# EEZ_DIB_MCU_r1B1.net
KiCad netlist of a schematic drawn in EAGLE
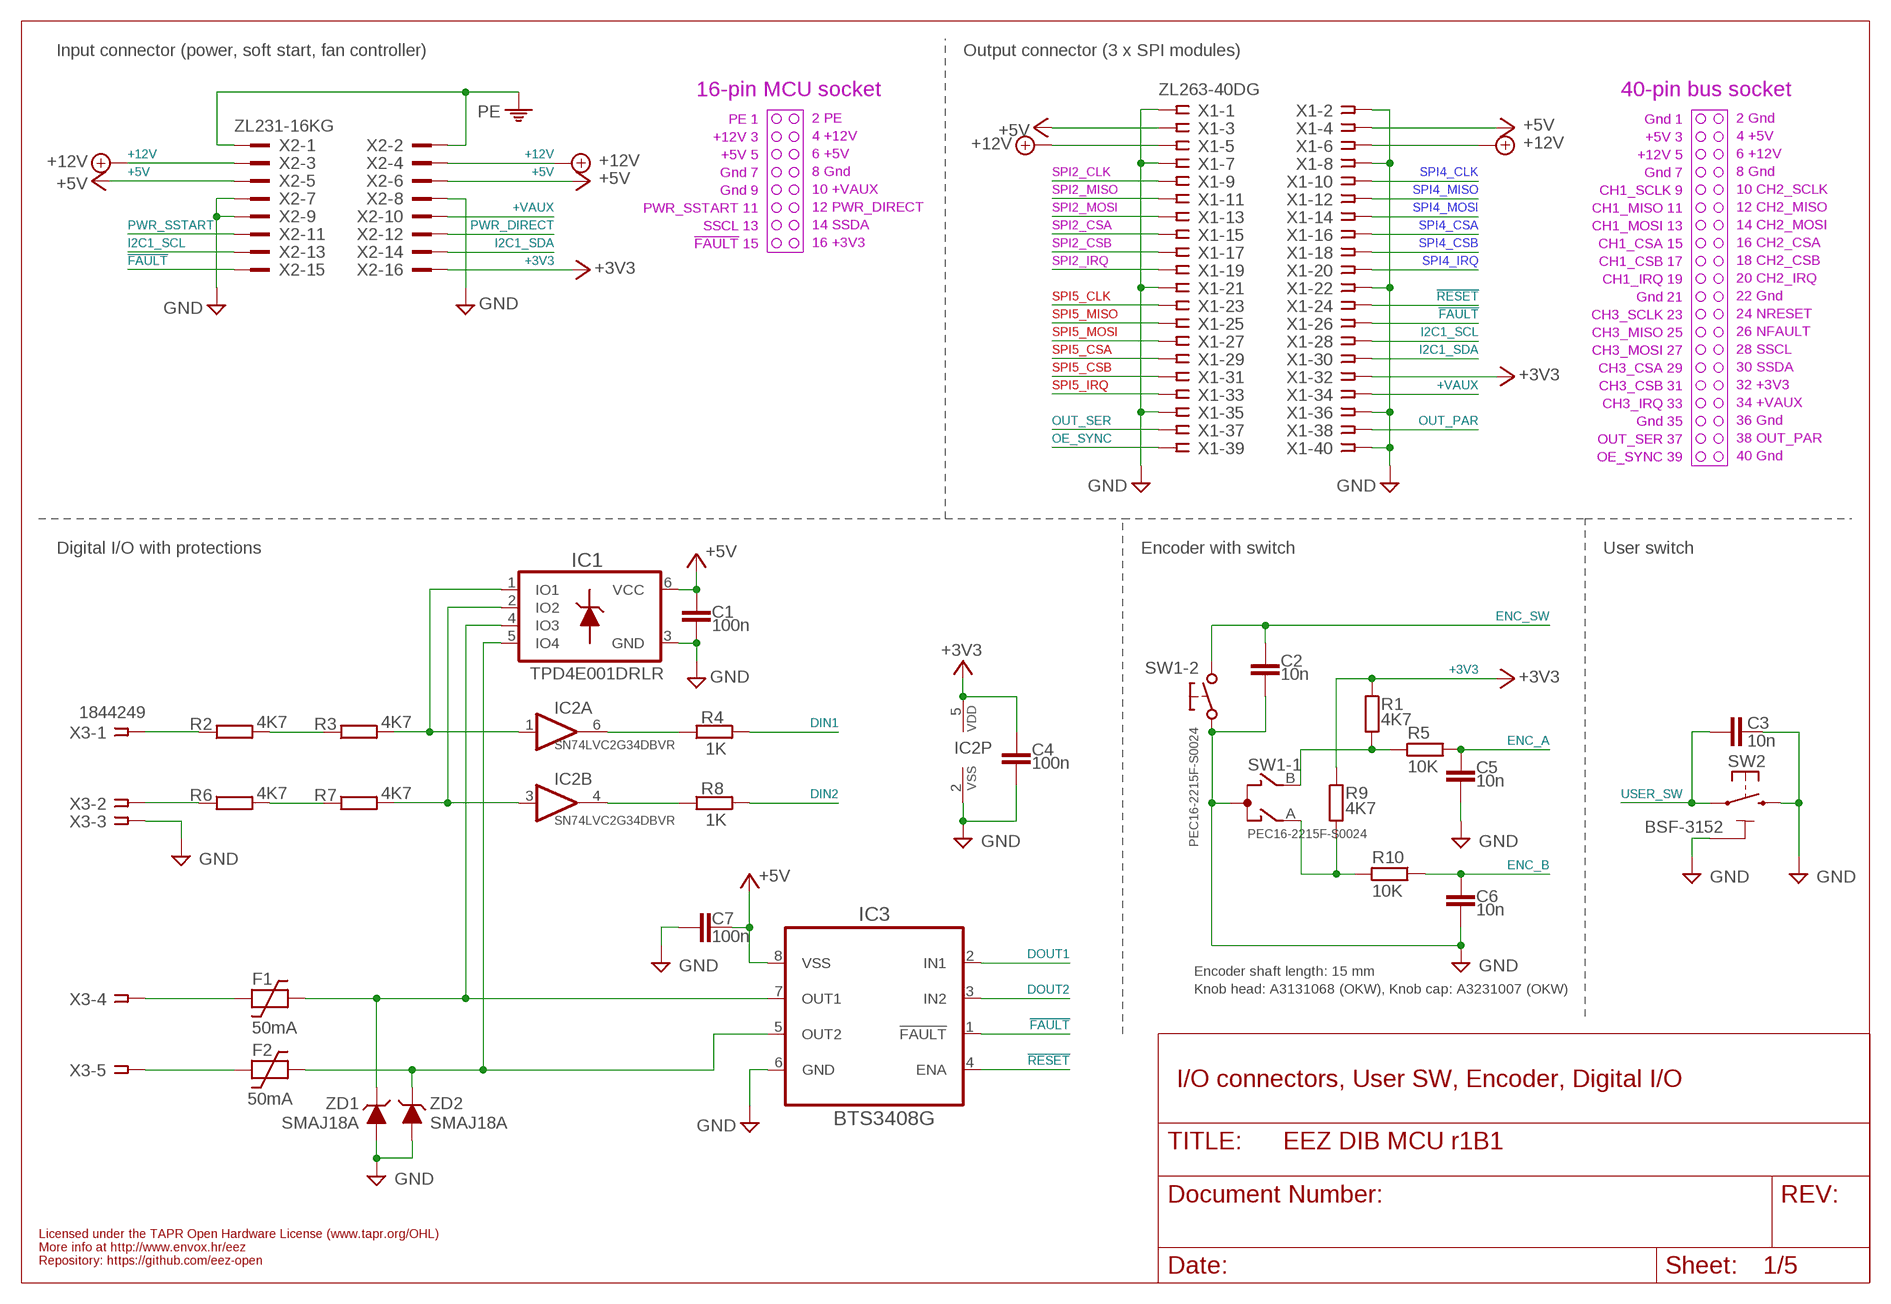
[diagram p0: schematic, sheet 1]
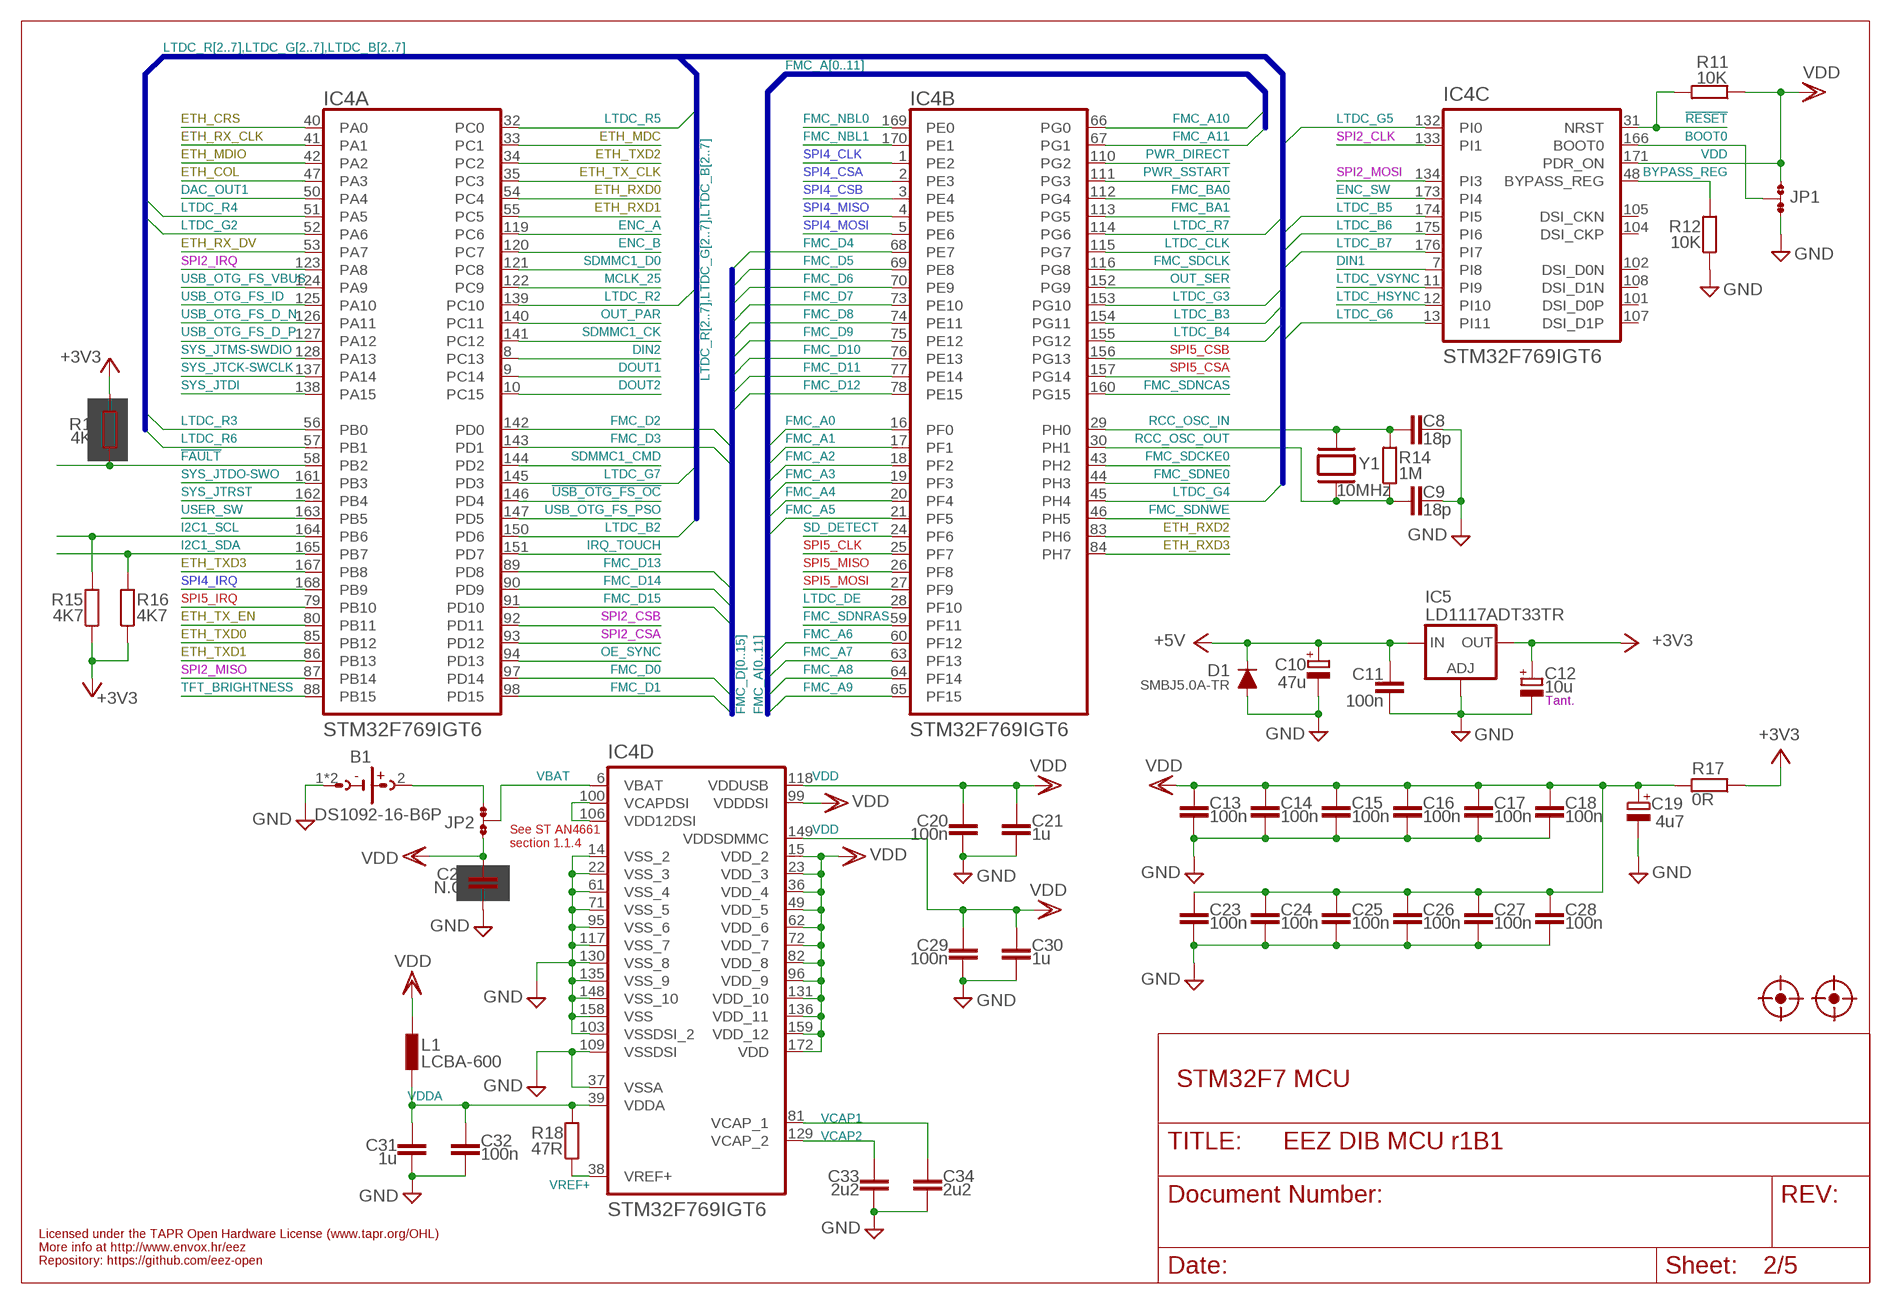
[diagram p1: schematic, sheet 2]
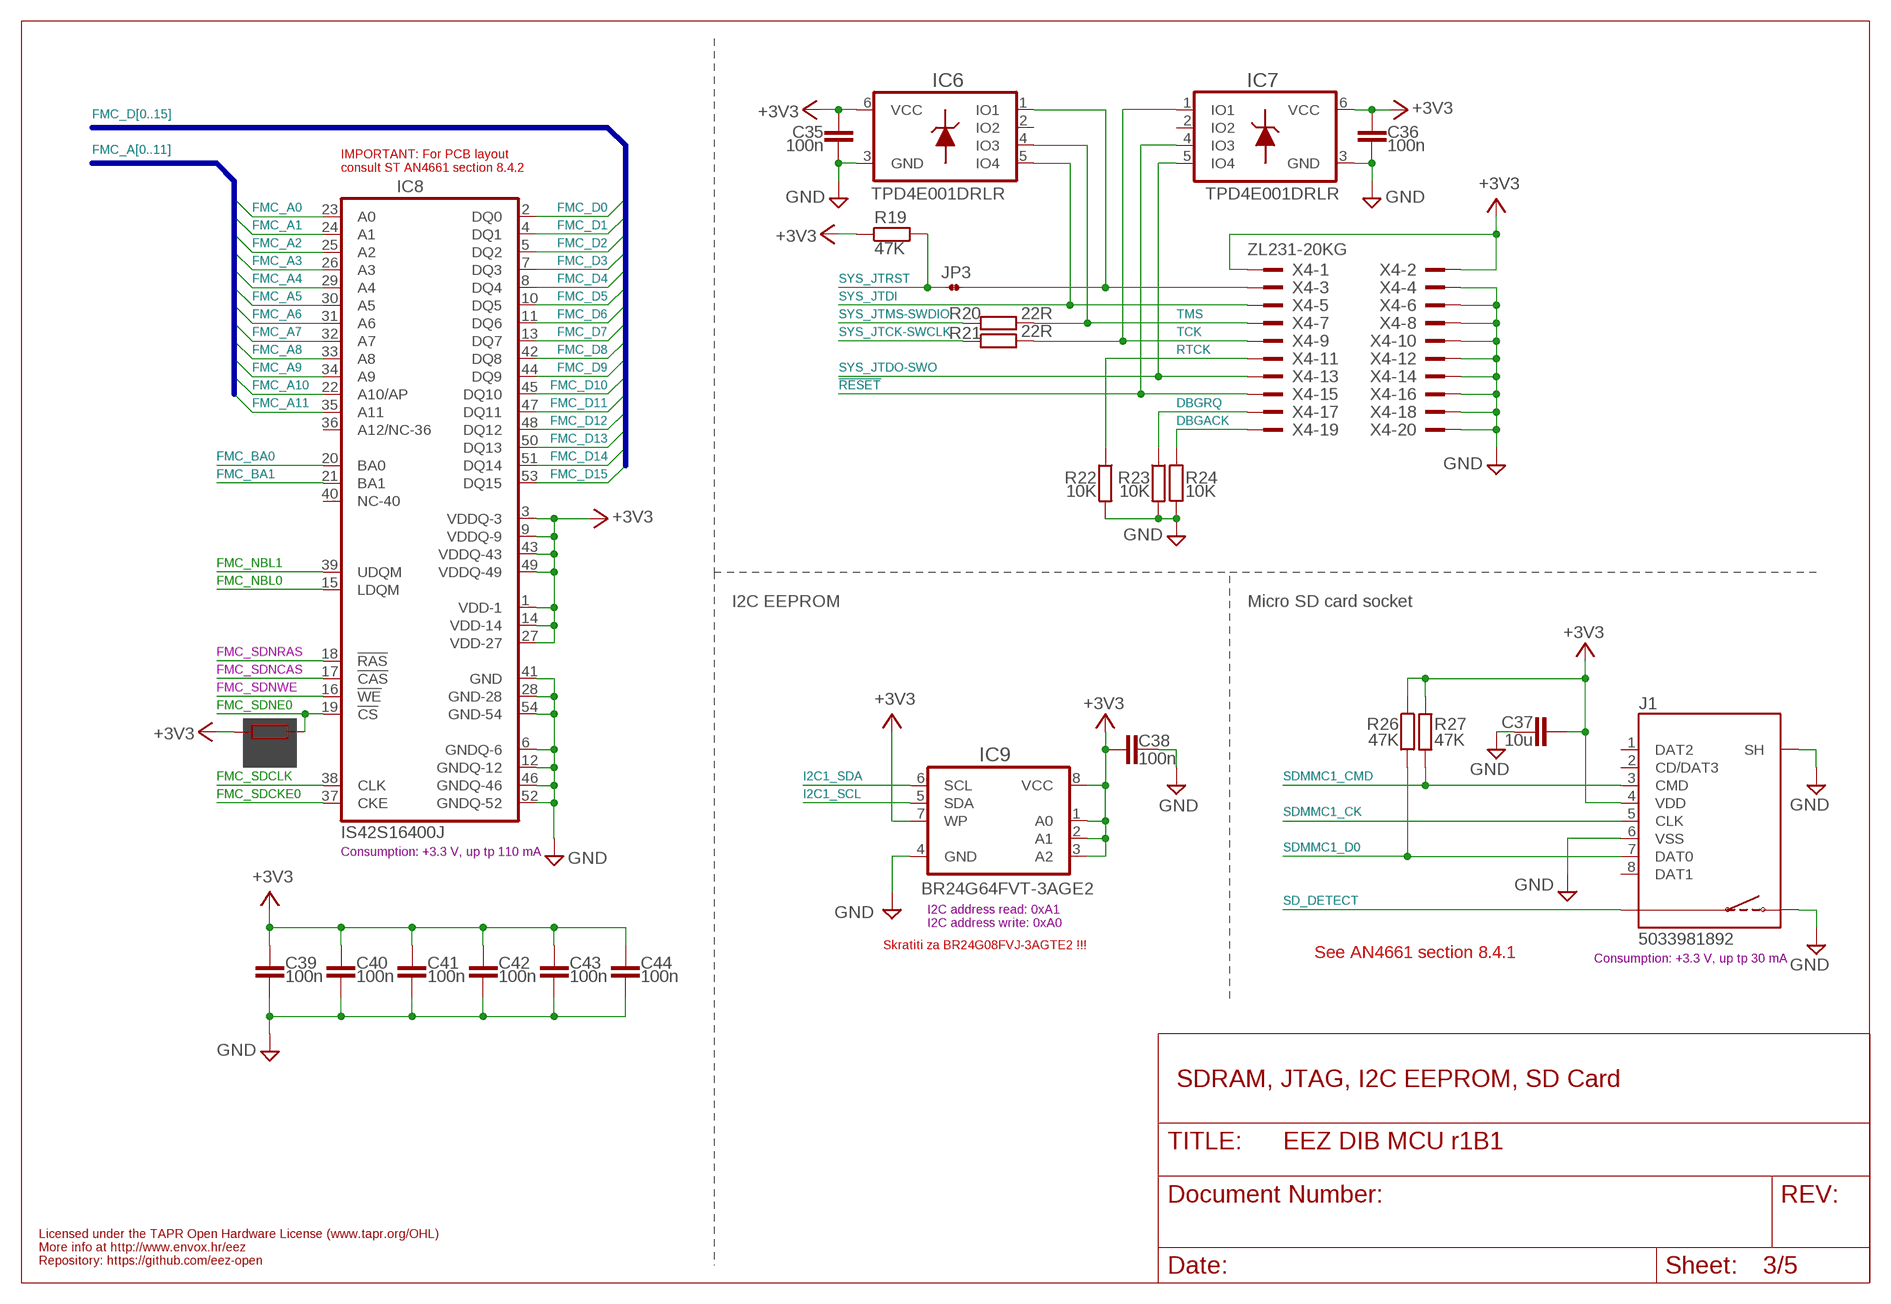
[diagram p2: schematic, sheet 3]
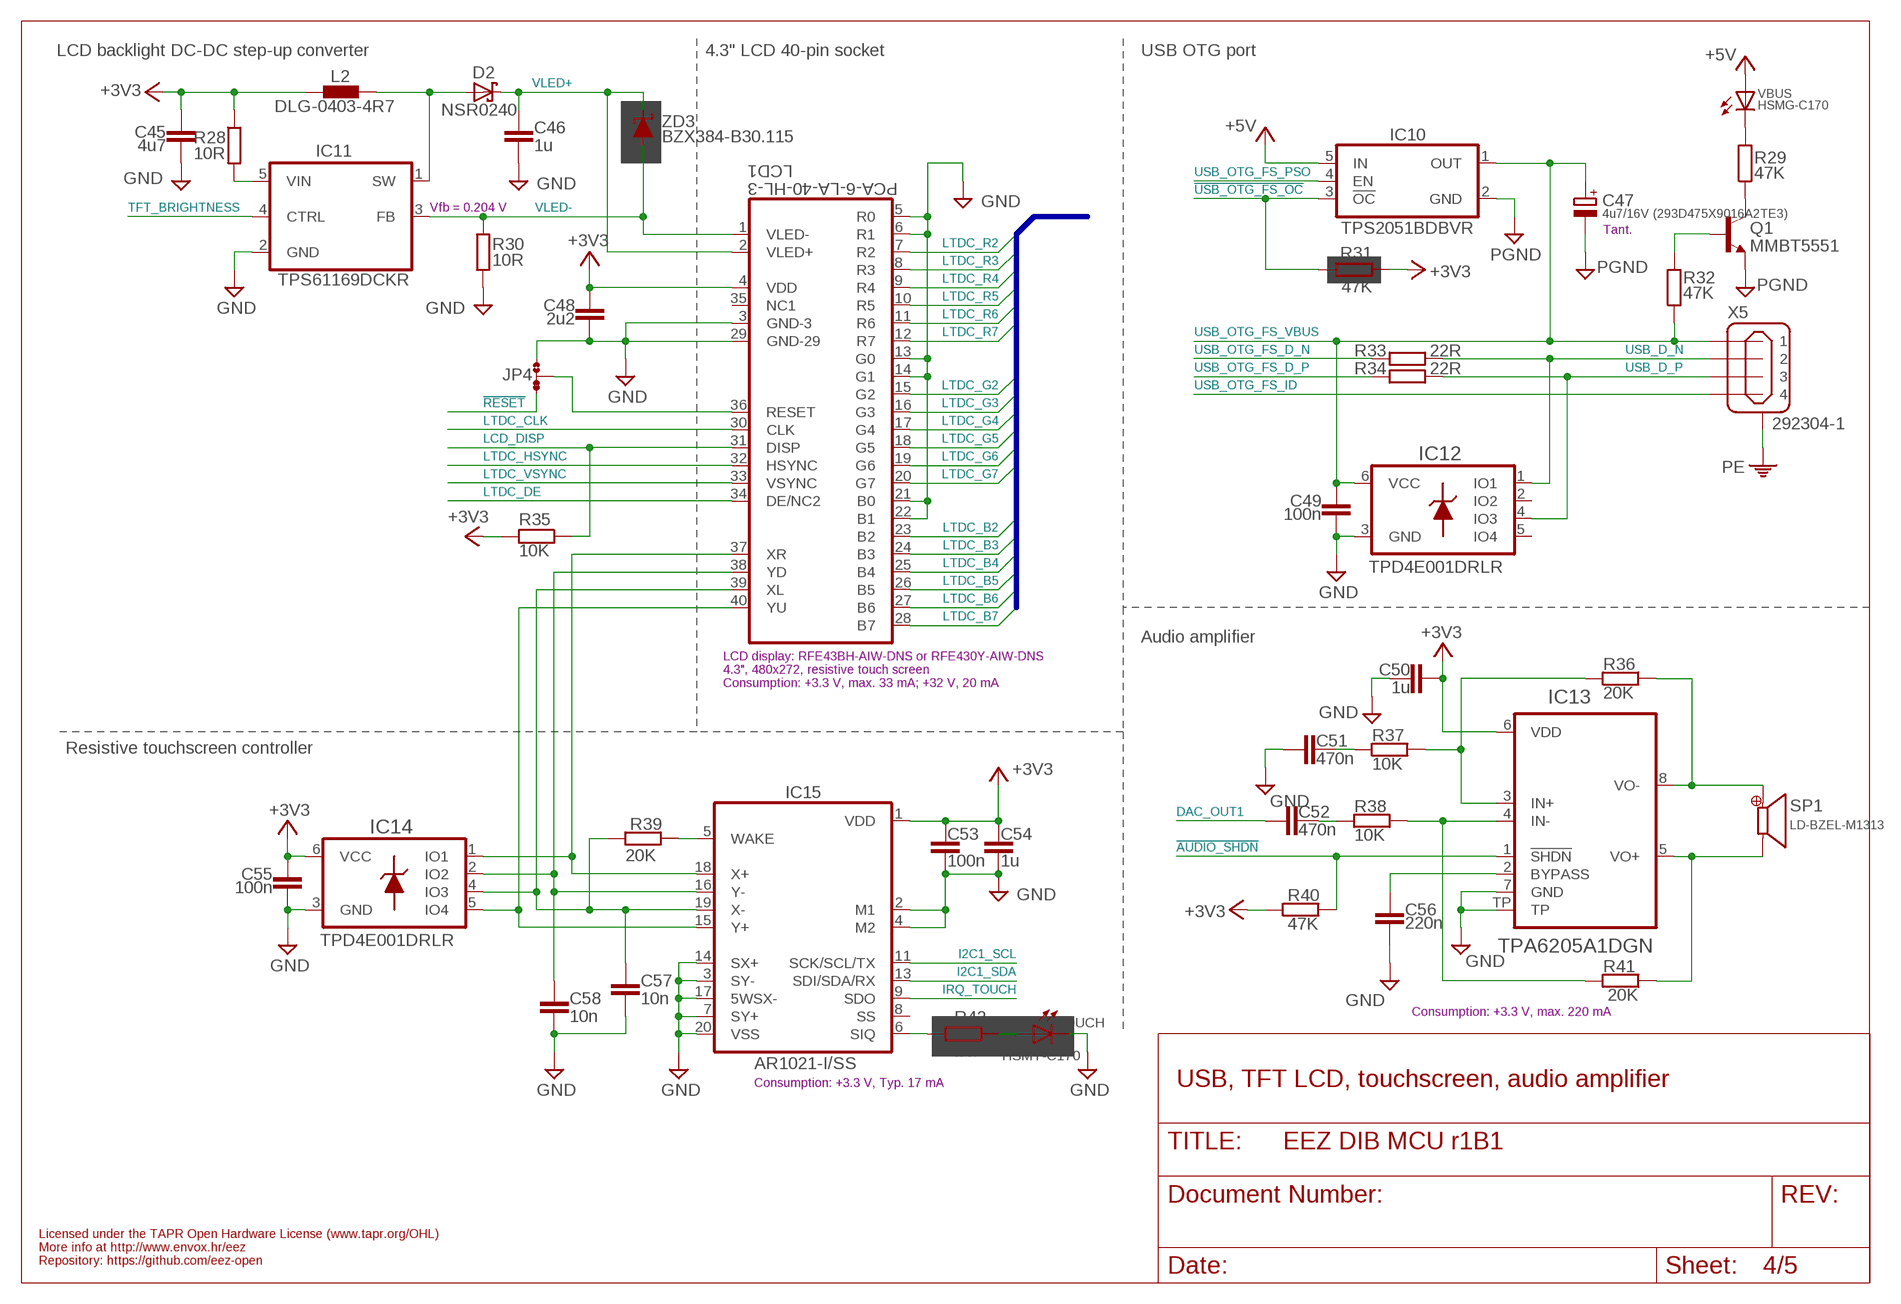
[diagram p3: schematic, sheet 4]
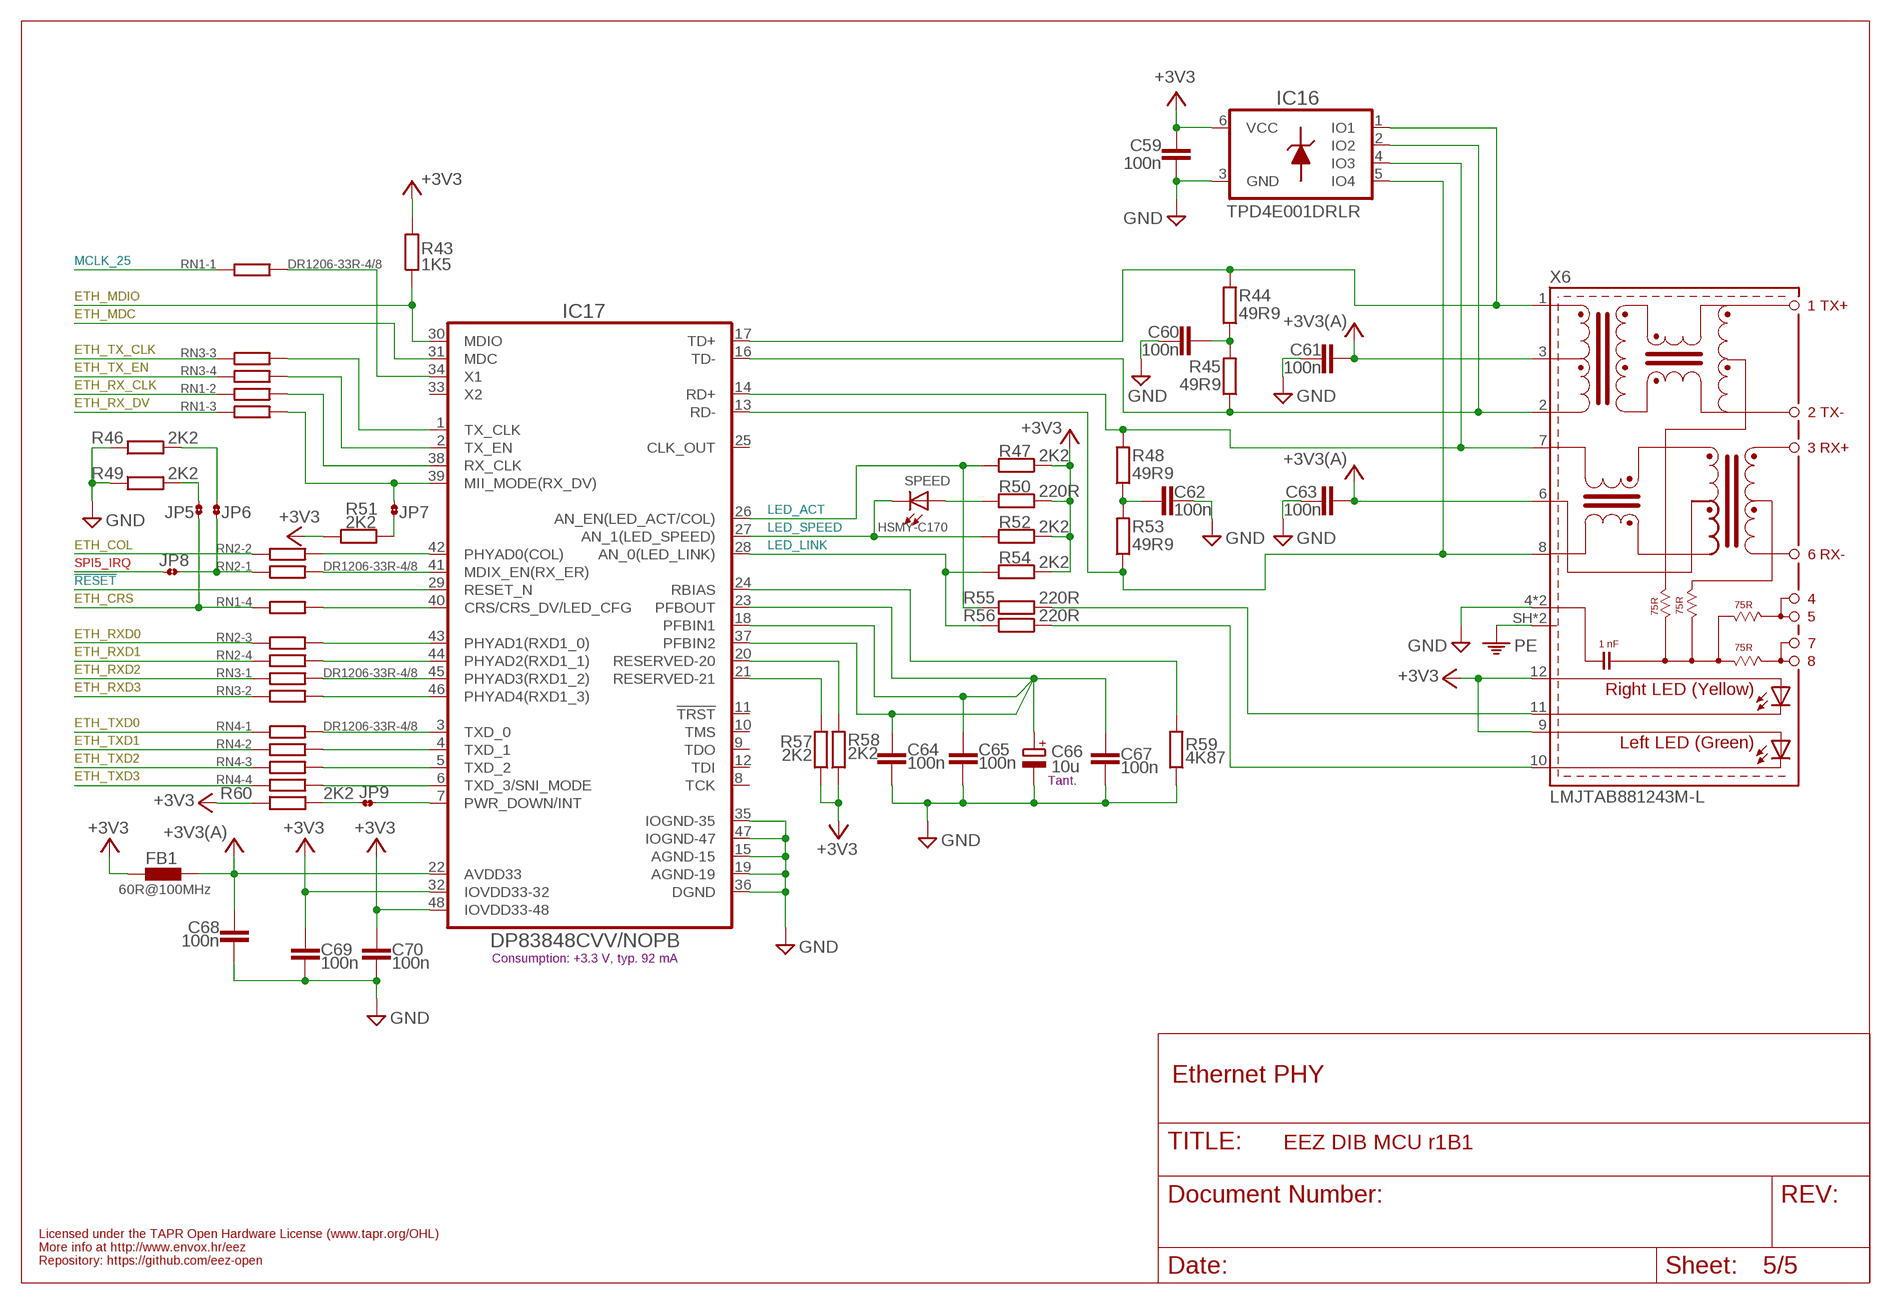
[diagram p4: schematic, sheet 5]

(export (version "E")
  (design (tool "Eeschema 10.0.6"))
  (components
    (comp (ref "B1")
      (value "DS1092-16-B6P")
      (footprint "eagle-import:DS1092-16-B6P")
      (libsource (lib "eagle-import") (part "CELL_BATTERY-THT20MM"))
    )
    (comp (ref "C8")
      (value "18p")
      (footprint "eagle-import:C0603")
      (libsource (lib "eagle-import") (part "C-EUC0603"))
    )
    (comp (ref "C9")
      (value "18p")
      (footprint "eagle-import:C0603")
      (libsource (lib "eagle-import") (part "C-EUC0603"))
    )
    (comp (ref "C10")
      (value "47u")
      (footprint "eagle-import:CAPAE660X610N")
      (libsource (lib "eagle-import") (part "ECAPPANASONIC_H"))
    )
    (comp (ref "C11")
      (value "100n")
      (footprint "eagle-import:C0603")
      (libsource (lib "eagle-import") (part "C-EUC0603"))
    )
    (comp (ref "C12")
      (value "10u")
      (footprint "eagle-import:EC1206")
      (libsource (lib "eagle-import") (part "ECAP1206"))
    )
    (comp (ref "C13")
      (value "100n")
      (footprint "eagle-import:C0603")
      (libsource (lib "eagle-import") (part "C-EUC0603"))
    )
    (comp (ref "C14")
      (value "100n")
      (footprint "eagle-import:C0603")
      (libsource (lib "eagle-import") (part "C-EUC0603"))
    )
    (comp (ref "C15")
      (value "100n")
      (footprint "eagle-import:C0603")
      (libsource (lib "eagle-import") (part "C-EUC0603"))
    )
    (comp (ref "C16")
      (value "100n")
      (footprint "eagle-import:C0603")
      (libsource (lib "eagle-import") (part "C-EUC0603"))
    )
    (comp (ref "C17")
      (value "100n")
      (footprint "eagle-import:C0603")
      (libsource (lib "eagle-import") (part "C-EUC0603"))
    )
    (comp (ref "C18")
      (value "100n")
      (footprint "eagle-import:C0603")
      (libsource (lib "eagle-import") (part "C-EUC0603"))
    )
    (comp (ref "C19")
      (value "4u7")
      (footprint "eagle-import:EC1206")
      (libsource (lib "eagle-import") (part "ECAP1206"))
    )
    (comp (ref "C20")
      (value "100n")
      (footprint "eagle-import:C0603")
      (libsource (lib "eagle-import") (part "C-EUC0603"))
    )
    (comp (ref "C21")
      (value "1u")
      (footprint "eagle-import:C0805")
      (libsource (lib "eagle-import") (part "C-EUC0805"))
    )
    (comp (ref "C22")
      (value "N.C.")
      (footprint "eagle-import:C0603")
      (libsource (lib "eagle-import") (part "C-EUC0603"))
    )
    (comp (ref "C23")
      (value "100n")
      (footprint "eagle-import:C0603")
      (libsource (lib "eagle-import") (part "C-EUC0603"))
    )
    (comp (ref "C24")
      (value "100n")
      (footprint "eagle-import:C0603")
      (libsource (lib "eagle-import") (part "C-EUC0603"))
    )
    (comp (ref "C25")
      (value "100n")
      (footprint "eagle-import:C0603")
      (libsource (lib "eagle-import") (part "C-EUC0603"))
    )
    (comp (ref "C26")
      (value "100n")
      (footprint "eagle-import:C0603")
      (libsource (lib "eagle-import") (part "C-EUC0603"))
    )
    (comp (ref "C27")
      (value "100n")
      (footprint "eagle-import:C0603")
      (libsource (lib "eagle-import") (part "C-EUC0603"))
    )
    (comp (ref "C28")
      (value "100n")
      (footprint "eagle-import:C0603")
      (libsource (lib "eagle-import") (part "C-EUC0603"))
    )
    (comp (ref "C29")
      (value "100n")
      (footprint "eagle-import:C0603")
      (libsource (lib "eagle-import") (part "C-EUC0603"))
    )
    (comp (ref "C30")
      (value "1u")
      (footprint "eagle-import:C0805")
      (libsource (lib "eagle-import") (part "C-EUC0805"))
    )
    (comp (ref "C31")
      (value "1u")
      (footprint "eagle-import:C0805")
      (libsource (lib "eagle-import") (part "C-EUC0805"))
    )
    (comp (ref "C32")
      (value "100n")
      (footprint "eagle-import:C0603")
      (libsource (lib "eagle-import") (part "C-EUC0603"))
    )
    (comp (ref "C33")
      (value "2u2")
      (footprint "eagle-import:C0805")
      (libsource (lib "eagle-import") (part "C-EUC0805"))
    )
    (comp (ref "C34")
      (value "2u2")
      (footprint "eagle-import:C0805")
      (libsource (lib "eagle-import") (part "C-EUC0805"))
    )
    (comp (ref "D1")
      (value "SMBJ5.0A-TR")
      (footprint "eagle-import:DO214AA")
      (libsource (lib "eagle-import") (part "DIODEDO214AA"))
    )
    (comp (ref "FM1")
      (value "FIDUCIAL")
      (footprint "eagle-import:FIDUCIAL")
      (libsource (lib "eagle-import") (part "FIDUCIAL"))
    )
    (comp (ref "FM2")
      (value "FIDUCIAL")
      (footprint "eagle-import:FIDUCIAL")
      (libsource (lib "eagle-import") (part "FIDUCIAL"))
    )
    (comp (ref "IC4")
      (value "STM32F769IGT6")
      (footprint "eagle-import:LQFP-176_24X24MM")
      (fields
        (field (name "MANUFACTURER_PART_NUMBER") "stm32f769ixt")
        (field (name "COPYRIGHT") "Copyright C 2016 Accelerated Designs. All rights reserved")
      )
      (libsource (lib "eagle-import") (part "STM32F769IXT"))
    )
    (comp (ref "IC5")
      (value "LD1117ADT33TR")
      (footprint "eagle-import:DPACK")
      (libsource (lib "eagle-import") (part "LD117A?DT33TR"))
    )
    (comp (ref "JP1")
      (value "JP3-CUT")
      (footprint "eagle-import:JP3-CUT")
      (libsource (lib "eagle-import") (part "JP3-CUT"))
    )
    (comp (ref "JP2")
      (value "JP3-CUT")
      (footprint "eagle-import:JP3-CUT")
      (libsource (lib "eagle-import") (part "JP3-CUT"))
    )
    (comp (ref "L1")
      (value "LCBA-600")
      (footprint "eagle-import:BEAD0603")
      (libsource (lib "eagle-import") (part "FERRITE_BEAD0603"))
    )
    (comp (ref "R11")
      (value "10K")
      (footprint "eagle-import:R0805")
      (libsource (lib "eagle-import") (part "R-EU_R0805"))
    )
    (comp (ref "R12")
      (value "10K")
      (footprint "eagle-import:R0805")
      (libsource (lib "eagle-import") (part "R-EU_R0805"))
    )
    (comp (ref "R13")
      (value "4K7")
      (footprint "eagle-import:R0805")
      (libsource (lib "eagle-import") (part "R-EU_R0805"))
    )
    (comp (ref "R14")
      (value "1M")
      (footprint "eagle-import:R0805")
      (libsource (lib "eagle-import") (part "R-EU_R0805"))
    )
    (comp (ref "R15")
      (value "4K7")
      (footprint "eagle-import:R0805")
      (libsource (lib "eagle-import") (part "R-EU_R0805"))
    )
    (comp (ref "R16")
      (value "4K7")
      (footprint "eagle-import:R0805")
      (libsource (lib "eagle-import") (part "R-EU_R0805"))
    )
    (comp (ref "R17")
      (value "0R")
      (footprint "eagle-import:R0805")
      (libsource (lib "eagle-import") (part "R-EU_R0805"))
    )
    (comp (ref "R18")
      (value "47R")
      (footprint "eagle-import:R0805")
      (libsource (lib "eagle-import") (part "R-EU_R0805"))
    )
    (comp (ref "Y1")
      (value "10MHz")
      (footprint "eagle-import:HC-49_4H")
      (libsource (lib "eagle-import") (part "XTALSMD"))
    )
    (comp (ref "C59")
      (value "100n")
      (footprint "eagle-import:C0603")
      (libsource (lib "eagle-import") (part "C-EUC0603"))
    )
    (comp (ref "C60")
      (value "100n")
      (footprint "eagle-import:C0603")
      (libsource (lib "eagle-import") (part "C-EUC0603"))
    )
    (comp (ref "C61")
      (value "100n")
      (footprint "eagle-import:C0603")
      (libsource (lib "eagle-import") (part "C-EUC0603"))
    )
    (comp (ref "C62")
      (value "100n")
      (footprint "eagle-import:C0603")
      (libsource (lib "eagle-import") (part "C-EUC0603"))
    )
    (comp (ref "C63")
      (value "100n")
      (footprint "eagle-import:C0603")
      (libsource (lib "eagle-import") (part "C-EUC0603"))
    )
    (comp (ref "C64")
      (value "100n")
      (footprint "eagle-import:C0603")
      (libsource (lib "eagle-import") (part "C-EUC0603"))
    )
    (comp (ref "C65")
      (value "100n")
      (footprint "eagle-import:C0603")
      (libsource (lib "eagle-import") (part "C-EUC0603"))
    )
    (comp (ref "C66")
      (value "10u")
      (footprint "eagle-import:EC1206")
      (libsource (lib "eagle-import") (part "ECAP1206"))
    )
    (comp (ref "C67")
      (value "100n")
      (footprint "eagle-import:C0603")
      (libsource (lib "eagle-import") (part "C-EUC0603"))
    )
    (comp (ref "C68")
      (value "100n")
      (footprint "eagle-import:C0603")
      (libsource (lib "eagle-import") (part "C-EUC0603"))
    )
    (comp (ref "C69")
      (value "100n")
      (footprint "eagle-import:C0603")
      (libsource (lib "eagle-import") (part "C-EUC0603"))
    )
    (comp (ref "C70")
      (value "100n")
      (footprint "eagle-import:C0603")
      (libsource (lib "eagle-import") (part "C-EUC0603"))
    )
    (comp (ref "FB1")
      (value "60R@100MHz")
      (footprint "eagle-import:BEAD0603")
      (libsource (lib "eagle-import") (part "FERRITE_BEAD0603"))
    )
    (comp (ref "IC16")
      (value "TPD4E001DRLR")
      (footprint "eagle-import:DRL6")
      (libsource (lib "eagle-import") (part "TPD4E001-DRL"))
    )
    (comp (ref "IC17")
      (value "DP83848CVV/NOPB")
      (footprint "eagle-import:PT48")
      (libsource (lib "eagle-import") (part "DP83848CVV/NOPB"))
    )
    (comp (ref "JP5")
      (value "JP2-CUT")
      (footprint "eagle-import:JP2-CUT")
      (libsource (lib "eagle-import") (part "JP2-CUT"))
    )
    (comp (ref "JP6")
      (value "JP2-CUT")
      (footprint "eagle-import:JP2-CUT")
      (libsource (lib "eagle-import") (part "JP2-CUT"))
    )
    (comp (ref "JP7")
      (value "JP2-CUT")
      (footprint "eagle-import:JP2-CUT")
      (libsource (lib "eagle-import") (part "JP2-CUT"))
    )
    (comp (ref "JP8")
      (value "JP2-CUT")
      (footprint "eagle-import:JP2-CUT")
      (libsource (lib "eagle-import") (part "JP2-CUT"))
    )
    (comp (ref "JP9")
      (value "JP2-NOCUT")
      (footprint "eagle-import:JP2-NOCUT")
      (libsource (lib "eagle-import") (part "JP2-NOCUT"))
    )
    (comp (ref "R43")
      (value "1K5")
      (footprint "eagle-import:R0805")
      (libsource (lib "eagle-import") (part "R-EU_R0805"))
    )
    (comp (ref "R44")
      (value "49R9")
      (footprint "eagle-import:R0805")
      (libsource (lib "eagle-import") (part "R-EU_R0805"))
    )
    (comp (ref "R45")
      (value "49R9")
      (footprint "eagle-import:R0805")
      (libsource (lib "eagle-import") (part "R-EU_R0805"))
    )
    (comp (ref "R46")
      (value "2K2")
      (footprint "eagle-import:R0805")
      (libsource (lib "eagle-import") (part "R-EU_R0805"))
    )
    (comp (ref "R47")
      (value "2K2")
      (footprint "eagle-import:R0805")
      (libsource (lib "eagle-import") (part "R-EU_R0805"))
    )
    (comp (ref "R48")
      (value "49R9")
      (footprint "eagle-import:R0805")
      (libsource (lib "eagle-import") (part "R-EU_R0805"))
    )
    (comp (ref "R49")
      (value "2K2")
      (footprint "eagle-import:R0805")
      (libsource (lib "eagle-import") (part "R-EU_R0805"))
    )
    (comp (ref "R50")
      (value "220R")
      (footprint "eagle-import:R0805")
      (libsource (lib "eagle-import") (part "R-EU_R0805"))
    )
    (comp (ref "R51")
      (value "2K2")
      (footprint "eagle-import:R0805")
      (libsource (lib "eagle-import") (part "R-EU_R0805"))
    )
    (comp (ref "R52")
      (value "2K2")
      (footprint "eagle-import:R0805")
      (libsource (lib "eagle-import") (part "R-EU_R0805"))
    )
    (comp (ref "R53")
      (value "49R9")
      (footprint "eagle-import:R0805")
      (libsource (lib "eagle-import") (part "R-EU_R0805"))
    )
    (comp (ref "R54")
      (value "2K2")
      (footprint "eagle-import:R0805")
      (libsource (lib "eagle-import") (part "R-EU_R0805"))
    )
    (comp (ref "R55")
      (value "220R")
      (footprint "eagle-import:R0805")
      (libsource (lib "eagle-import") (part "R-EU_R0805"))
    )
    (comp (ref "R56")
      (value "220R")
      (footprint "eagle-import:R0805")
      (libsource (lib "eagle-import") (part "R-EU_R0805"))
    )
    (comp (ref "R57")
      (value "2K2")
      (footprint "eagle-import:R0805")
      (libsource (lib "eagle-import") (part "R-EU_R0805"))
    )
    (comp (ref "R58")
      (value "2K2")
      (footprint "eagle-import:R0805")
      (libsource (lib "eagle-import") (part "R-EU_R0805"))
    )
    (comp (ref "R59")
      (value "4K87")
      (footprint "eagle-import:R0603")
      (libsource (lib "eagle-import") (part "R-EU_R0603"))
    )
    (comp (ref "R60")
      (value "2K2")
      (footprint "eagle-import:R0805")
      (libsource (lib "eagle-import") (part "R-EU_R0805"))
    )
    (comp (ref "RN1")
      (value "DR1206-33R-4/8")
      (footprint "eagle-import:CAY16")
      (libsource (lib "eagle-import") (part "R_ARRAY4"))
    )
    (comp (ref "RN2")
      (value "DR1206-33R-4/8")
      (footprint "eagle-import:CAY16")
      (libsource (lib "eagle-import") (part "R_ARRAY4"))
    )
    (comp (ref "RN3")
      (value "DR1206-33R-4/8")
      (footprint "eagle-import:CAY16")
      (libsource (lib "eagle-import") (part "R_ARRAY4"))
    )
    (comp (ref "RN4")
      (value "DR1206-33R-4/8")
      (footprint "eagle-import:CAY16")
      (libsource (lib "eagle-import") (part "R_ARRAY4"))
    )
    (comp (ref "SPEED")
      (value "HSMY-C170")
      (footprint "eagle-import:LED_0805")
      (libsource (lib "eagle-import") (part "LED0805"))
    )
    (comp (ref "X6")
      (value "LMJTAB881243M-L")
      (footprint "eagle-import:RJ45-TRAFO-LED")
      (libsource (lib "eagle-import") (part "RJ45-TRAFO-LED"))
    )
    (comp (ref "C1")
      (value "100n")
      (footprint "eagle-import:C0603")
      (libsource (lib "eagle-import") (part "C-EUC0603"))
    )
    (comp (ref "C2")
      (value "10n")
      (footprint "eagle-import:C0805")
      (libsource (lib "eagle-import") (part "C-EUC0805"))
    )
    (comp (ref "C3")
      (value "10n")
      (footprint "eagle-import:C0805")
      (libsource (lib "eagle-import") (part "C-EUC0805"))
    )
    (comp (ref "C4")
      (value "100n")
      (footprint "eagle-import:C0603")
      (libsource (lib "eagle-import") (part "C-EUC0603"))
    )
    (comp (ref "C5")
      (value "10n")
      (footprint "eagle-import:C0805")
      (libsource (lib "eagle-import") (part "C-EUC0805"))
    )
    (comp (ref "C6")
      (value "10n")
      (footprint "eagle-import:C0805")
      (libsource (lib "eagle-import") (part "C-EUC0805"))
    )
    (comp (ref "C7")
      (value "100n")
      (footprint "eagle-import:C0603")
      (libsource (lib "eagle-import") (part "C-EUC0603"))
    )
    (comp (ref "F1")
      (value "50mA")
      (footprint "eagle-import:F1210")
      (libsource (lib "eagle-import") (part "FUSE_RESETTABLE21210"))
    )
    (comp (ref "F2")
      (value "50mA")
      (footprint "eagle-import:F1210")
      (libsource (lib "eagle-import") (part "FUSE_RESETTABLE21210"))
    )
    (comp (ref "IC1")
      (value "TPD4E001DRLR")
      (footprint "eagle-import:DRL6")
      (libsource (lib "eagle-import") (part "TPD4E001-DRL"))
    )
    (comp (ref "IC2")
      (value "SN74LVC2G34DBVR")
      (footprint "eagle-import:DBV6")
      (libsource (lib "eagle-import") (part "SN74LVC2G34DBVR"))
    )
    (comp (ref "IC3")
      (value "BTS3408G")
      (footprint "eagle-import:SOIC127P600X173-8N")
      (libsource (lib "eagle-import") (part "BTS3408G"))
    )
    (comp (ref "R1")
      (value "4K7")
      (footprint "eagle-import:R0805")
      (libsource (lib "eagle-import") (part "R-EU_R0805"))
    )
    (comp (ref "R2")
      (value "4K7")
      (footprint "eagle-import:R0805")
      (libsource (lib "eagle-import") (part "R-EU_R0805"))
    )
    (comp (ref "R3")
      (value "4K7")
      (footprint "eagle-import:R0805")
      (libsource (lib "eagle-import") (part "R-EU_R0805"))
    )
    (comp (ref "R4")
      (value "1K")
      (footprint "eagle-import:R0805")
      (libsource (lib "eagle-import") (part "R-EU_R0805"))
    )
    (comp (ref "R5")
      (value "10K")
      (footprint "eagle-import:R0805")
      (libsource (lib "eagle-import") (part "R-EU_R0805"))
    )
    (comp (ref "R6")
      (value "4K7")
      (footprint "eagle-import:R0805")
      (libsource (lib "eagle-import") (part "R-EU_R0805"))
    )
    (comp (ref "R7")
      (value "4K7")
      (footprint "eagle-import:R0805")
      (libsource (lib "eagle-import") (part "R-EU_R0805"))
    )
    (comp (ref "R8")
      (value "1K")
      (footprint "eagle-import:R0805")
      (libsource (lib "eagle-import") (part "R-EU_R0805"))
    )
    (comp (ref "R9")
      (value "4K7")
      (footprint "eagle-import:R0805")
      (libsource (lib "eagle-import") (part "R-EU_R0805"))
    )
    (comp (ref "R10")
      (value "10K")
      (footprint "eagle-import:R0805")
      (libsource (lib "eagle-import") (part "R-EU_R0805"))
    )
    (comp (ref "SW1")
      (value "PEC16-2215F-S0024")
      (footprint "eagle-import:PEC16-2215F")
      (libsource (lib "eagle-import") (part "ENCODER_SW-PEC16"))
    )
    (comp (ref "SW2")
      (value "BSF-3152")
      (footprint "eagle-import:BSF-315X")
      (libsource (lib "eagle-import") (part "BSF-315X"))
    )
    (comp (ref "X1")
      (value "ZL263-40DG")
      (footprint "eagle-import:ZL263-40DG")
      (libsource (lib "eagle-import") (part "ZL263-40DG"))
    )
    (comp (ref "X2")
      (value "ZL231-16KG")
      (footprint "eagle-import:ML16L")
      (libsource (lib "eagle-import") (part "IDC-16PIN-ANGLED"))
    )
    (comp (ref "X3")
      (value "1844249")
      (footprint "eagle-import:MC1,5_5-G-3,5")
      (libsource (lib "eagle-import") (part "MC1,5/5-G-3,5"))
    )
    (comp (ref "ZD1")
      (value "SMAJ18A")
      (footprint "eagle-import:DO214AC")
      (libsource (lib "eagle-import") (part "PSMAXX"))
    )
    (comp (ref "ZD2")
      (value "SMAJ18A")
      (footprint "eagle-import:DO214AC")
      (libsource (lib "eagle-import") (part "PSMAXX"))
    )
    (comp (ref "C45")
      (value "4u7")
      (footprint "eagle-import:C1206")
      (libsource (lib "eagle-import") (part "C-EUC1206"))
    )
    (comp (ref "C46")
      (value "1u")
      (footprint "eagle-import:C0805")
      (libsource (lib "eagle-import") (part "C-EUC0805"))
    )
    (comp (ref "C47")
      (value "4u7/16V (293D475X9016A2TE3)")
      (footprint "eagle-import:EC1206")
      (libsource (lib "eagle-import") (part "ECAP1206"))
    )
    (comp (ref "C48")
      (value "2u2")
      (footprint "eagle-import:C0805")
      (libsource (lib "eagle-import") (part "C-EUC0805"))
    )
    (comp (ref "C49")
      (value "100n")
      (footprint "eagle-import:C0603")
      (libsource (lib "eagle-import") (part "C-EUC0603"))
    )
    (comp (ref "C50")
      (value "1u")
      (footprint "eagle-import:C0805")
      (libsource (lib "eagle-import") (part "C-EUC0805"))
    )
    (comp (ref "C51")
      (value "470n")
      (footprint "eagle-import:C0805")
      (libsource (lib "eagle-import") (part "C-EUC0805"))
    )
    (comp (ref "C52")
      (value "470n")
      (footprint "eagle-import:C0805")
      (libsource (lib "eagle-import") (part "C-EUC0805"))
    )
    (comp (ref "C53")
      (value "100n")
      (footprint "eagle-import:C0603")
      (libsource (lib "eagle-import") (part "C-EUC0603"))
    )
    (comp (ref "C54")
      (value "1u")
      (footprint "eagle-import:C0805")
      (libsource (lib "eagle-import") (part "C-EUC0805"))
    )
    (comp (ref "C55")
      (value "100n")
      (footprint "eagle-import:C0603")
      (libsource (lib "eagle-import") (part "C-EUC0603"))
    )
    (comp (ref "C56")
      (value "220n")
      (footprint "eagle-import:C0805")
      (libsource (lib "eagle-import") (part "C-EUC0805"))
    )
    (comp (ref "C57")
      (value "10n")
      (footprint "eagle-import:C0805")
      (libsource (lib "eagle-import") (part "C-EUC0805"))
    )
    (comp (ref "C58")
      (value "10n")
      (footprint "eagle-import:C0805")
      (libsource (lib "eagle-import") (part "C-EUC0805"))
    )
    (comp (ref "D2")
      (value "NSR0240")
      (footprint "eagle-import:SOD123")
      (libsource (lib "eagle-import") (part "SCHOTTKYSOD123"))
    )
    (comp (ref "IC10")
      (value "TPS2051BDBVR")
      (footprint "eagle-import:DBV5")
      (libsource (lib "eagle-import") (part "TPS2051B"))
    )
    (comp (ref "IC11")
      (value "TPS61169DCKR")
      (footprint "eagle-import:DCK5")
      (fields (field (name "MANUFACTURER") "Texas Instruments"))
      (libsource (lib "eagle-import") (part "TPS61169DCKR"))
    )
    (comp (ref "IC12")
      (value "TPD4E001DRLR")
      (footprint "eagle-import:DRL6")
      (libsource (lib "eagle-import") (part "TPD4E001-DRL"))
    )
    (comp (ref "IC13")
      (value "TPA6205A1DGN")
      (footprint "eagle-import:SOP65P490X110-9N")
      (libsource (lib "eagle-import") (part "TPA6205"))
    )
    (comp (ref "IC14")
      (value "TPD4E001DRLR")
      (footprint "eagle-import:DRL6")
      (libsource (lib "eagle-import") (part "TPD4E001-DRL"))
    )
    (comp (ref "IC15")
      (value "AR1021-I/SS")
      (footprint "eagle-import:SOP65P780X200-20N")
      (libsource (lib "eagle-import") (part "AR1021-I/SS"))
    )
    (comp (ref "JP4")
      (value "JP3-CUT")
      (footprint "eagle-import:JP3-CUT")
      (libsource (lib "eagle-import") (part "JP3-CUT"))
    )
    (comp (ref "L2")
      (value "DLG-0403-4R7")
      (footprint "eagle-import:DE0403")
      (libsource (lib "eagle-import") (part "DE0403"))
    )
    (comp (ref "LCD1")
      (value "PCA-6-LA-40-HL-3")
      (footprint "eagle-import:FPC_40")
      (libsource (lib "eagle-import") (part "RFE430Y-AIW-DNS"))
    )
    (comp (ref "Q1")
      (value "MMBT5551")
      (footprint "eagle-import:SOT23-BEC")
      (libsource (lib "eagle-import") (part "-NPN-SOT23-BECMMBT5551LT1"))
    )
    (comp (ref "R28")
      (value "10R")
      (footprint "eagle-import:R0805")
      (libsource (lib "eagle-import") (part "R-EU_R0805"))
    )
    (comp (ref "R29")
      (value "47K")
      (footprint "eagle-import:R0805")
      (libsource (lib "eagle-import") (part "R-EU_R0805"))
    )
    (comp (ref "R30")
      (value "10R")
      (footprint "eagle-import:R0805")
      (libsource (lib "eagle-import") (part "R-EU_R0805"))
    )
    (comp (ref "R31")
      (value "47K")
      (footprint "eagle-import:R0805")
      (libsource (lib "eagle-import") (part "R-EU_R0805"))
    )
    (comp (ref "R32")
      (value "47K")
      (footprint "eagle-import:R0805")
      (libsource (lib "eagle-import") (part "R-EU_R0805"))
    )
    (comp (ref "R33")
      (value "22R")
      (footprint "eagle-import:R0805")
      (libsource (lib "eagle-import") (part "R-EU_R0805"))
    )
    (comp (ref "R34")
      (value "22R")
      (footprint "eagle-import:R0805")
      (libsource (lib "eagle-import") (part "R-EU_R0805"))
    )
    (comp (ref "R35")
      (value "10K")
      (footprint "eagle-import:R0805")
      (libsource (lib "eagle-import") (part "R-EU_R0805"))
    )
    (comp (ref "R36")
      (value "20K")
      (footprint "eagle-import:R0805")
      (libsource (lib "eagle-import") (part "R-EU_R0805"))
    )
    (comp (ref "R37")
      (value "10K")
      (footprint "eagle-import:R0805")
      (libsource (lib "eagle-import") (part "R-EU_R0805"))
    )
    (comp (ref "R38")
      (value "10K")
      (footprint "eagle-import:R0805")
      (libsource (lib "eagle-import") (part "R-EU_R0805"))
    )
    (comp (ref "R39")
      (value "20K")
      (footprint "eagle-import:R0805")
      (libsource (lib "eagle-import") (part "R-EU_R0805"))
    )
    (comp (ref "R40")
      (value "47K")
      (footprint "eagle-import:R0805")
      (libsource (lib "eagle-import") (part "R-EU_R0805"))
    )
    (comp (ref "R41")
      (value "20K")
      (footprint "eagle-import:R0805")
      (libsource (lib "eagle-import") (part "R-EU_R0805"))
    )
    (comp (ref "R42")
      (value "4K7")
      (footprint "eagle-import:R0805")
      (libsource (lib "eagle-import") (part "R-EU_R0805"))
    )
    (comp (ref "SP1")
      (value "LD-BZEL-M1313")
      (footprint "eagle-import:LD-BZEL-M1313")
      (libsource (lib "eagle-import") (part "LD-BZEL-M1313"))
    )
    (comp (ref "TOUCH")
      (value "HSMY-C170")
      (footprint "eagle-import:LED_0805")
      (libsource (lib "eagle-import") (part "LED0805"))
    )
    (comp (ref "VBUS")
      (value "HSMG-C170")
      (footprint "eagle-import:LED_0805")
      (libsource (lib "eagle-import") (part "LED0805"))
    )
    (comp (ref "X5")
      (value "292304-1")
      (footprint "eagle-import:USB-B")
      (libsource (lib "eagle-import") (part "USB-B292304-1"))
    )
    (comp (ref "ZD3")
      (value "BZX384-B30.115")
      (footprint "eagle-import:SOD323-W")
      (libsource (lib "eagle-import") (part "ZENER-DIODESOD323"))
    )
    (comp (ref "C35")
      (value "100n")
      (footprint "eagle-import:C0603")
      (libsource (lib "eagle-import") (part "C-EUC0603"))
    )
    (comp (ref "C36")
      (value "100n")
      (footprint "eagle-import:C0603")
      (libsource (lib "eagle-import") (part "C-EUC0603"))
    )
    (comp (ref "C37")
      (value "10u")
      (footprint "eagle-import:C1210")
      (libsource (lib "eagle-import") (part "C-EUC1210"))
    )
    (comp (ref "C38")
      (value "100n")
      (footprint "eagle-import:C0603")
      (libsource (lib "eagle-import") (part "C-EUC0603"))
    )
    (comp (ref "C39")
      (value "100n")
      (footprint "eagle-import:C0603")
      (libsource (lib "eagle-import") (part "C-EUC0603"))
    )
    (comp (ref "C40")
      (value "100n")
      (footprint "eagle-import:C0603")
      (libsource (lib "eagle-import") (part "C-EUC0603"))
    )
    (comp (ref "C41")
      (value "100n")
      (footprint "eagle-import:C0603")
      (libsource (lib "eagle-import") (part "C-EUC0603"))
    )
    (comp (ref "C42")
      (value "100n")
      (footprint "eagle-import:C0603")
      (libsource (lib "eagle-import") (part "C-EUC0603"))
    )
    (comp (ref "C43")
      (value "100n")
      (footprint "eagle-import:C0603")
      (libsource (lib "eagle-import") (part "C-EUC0603"))
    )
    (comp (ref "C44")
      (value "100n")
      (footprint "eagle-import:C0603")
      (libsource (lib "eagle-import") (part "C-EUC0603"))
    )
    (comp (ref "IC6")
      (value "TPD4E001DRLR")
      (footprint "eagle-import:DRL6")
      (libsource (lib "eagle-import") (part "TPD4E001-DRL"))
    )
    (comp (ref "IC7")
      (value "TPD4E001DRLR")
      (footprint "eagle-import:DRL6")
      (libsource (lib "eagle-import") (part "TPD4E001-DRL"))
    )
    (comp (ref "IC8")
      (value "IS42S16400J")
      (footprint "eagle-import:TSOPII-54")
      (libsource (lib "eagle-import") (part "IS42S16400"))
    )
    (comp (ref "IC9")
      (value "BR24G64FVT-3AGE2")
      (footprint "eagle-import:PW8_TSSOP8")
      (libsource (lib "eagle-import") (part "BR24GXXX-TSSOP"))
    )
    (comp (ref "J1")
      (value "5033981892")
      (footprint "eagle-import:5033981892")
      (libsource (lib "eagle-import") (part "5033981892"))
    )
    (comp (ref "JP3")
      (value "JP2-NOCUT")
      (footprint "eagle-import:JP2-NOCUT")
      (libsource (lib "eagle-import") (part "JP2-NOCUT"))
    )
    (comp (ref "R19")
      (value "47K")
      (footprint "eagle-import:R0805")
      (libsource (lib "eagle-import") (part "R-EU_R0805"))
    )
    (comp (ref "R20")
      (value "22R")
      (footprint "eagle-import:R0805")
      (libsource (lib "eagle-import") (part "R-EU_R0805"))
    )
    (comp (ref "R21")
      (value "22R")
      (footprint "eagle-import:R0805")
      (libsource (lib "eagle-import") (part "R-EU_R0805"))
    )
    (comp (ref "R22")
      (value "10K")
      (footprint "eagle-import:R0805")
      (libsource (lib "eagle-import") (part "R-EU_R0805"))
    )
    (comp (ref "R23")
      (value "10K")
      (footprint "eagle-import:R0805")
      (libsource (lib "eagle-import") (part "R-EU_R0805"))
    )
    (comp (ref "R24")
      (value "10K")
      (footprint "eagle-import:R0805")
      (libsource (lib "eagle-import") (part "R-EU_R0805"))
    )
    (comp (ref "R25")
      (value "10K")
      (footprint "eagle-import:R0805")
      (libsource (lib "eagle-import") (part "R-EU_R0805"))
    )
    (comp (ref "R26")
      (value "47K")
      (footprint "eagle-import:R0805")
      (libsource (lib "eagle-import") (part "R-EU_R0805"))
    )
    (comp (ref "R27")
      (value "47K")
      (footprint "eagle-import:R0805")
      (libsource (lib "eagle-import") (part "R-EU_R0805"))
    )
    (comp (ref "X4")
      (value "ZL231-20KG")
      (footprint "eagle-import:ML20L")
      (libsource (lib "eagle-import") (part "IDC-20PIN-ANGLED"))
    )
  )
  (nets
    (net (code "1") (name "+3V3") (class "Default")
      (node (ref "C12") (pin "+") (pinfunction "+_+") (pintype "passive"))
      (node (ref "C35") (pin "1") (pinfunction "1_1") (pintype "passive"))
      (node (ref "C36") (pin "1") (pinfunction "1_1") (pintype "passive"))
      (node (ref "C37") (pin "1") (pinfunction "1_1") (pintype "passive"))
      (node (ref "C38") (pin "2") (pinfunction "2_2") (pintype "passive"))
      (node (ref "C39") (pin "1") (pinfunction "1_1") (pintype "passive"))
      (node (ref "C4") (pin "1") (pinfunction "1_1") (pintype "passive"))
      (node (ref "C40") (pin "1") (pinfunction "1_1") (pintype "passive"))
      (node (ref "C41") (pin "1") (pinfunction "1_1") (pintype "passive"))
      (node (ref "C42") (pin "1") (pinfunction "1_1") (pintype "passive"))
      (node (ref "C43") (pin "1") (pinfunction "1_1") (pintype "passive"))
      (node (ref "C44") (pin "1") (pinfunction "1_1") (pintype "passive"))
      (node (ref "C45") (pin "1") (pinfunction "1_1") (pintype "passive"))
      (node (ref "C48") (pin "1") (pinfunction "1_1") (pintype "passive"))
      (node (ref "C50") (pin "2") (pinfunction "2_2") (pintype "passive"))
      (node (ref "C53") (pin "2") (pinfunction "2_2") (pintype "passive"))
      (node (ref "C54") (pin "2") (pinfunction "2_2") (pintype "passive"))
      (node (ref "C55") (pin "2") (pinfunction "2_2") (pintype "passive"))
      (node (ref "C59") (pin "1") (pinfunction "1_1") (pintype "passive"))
      (node (ref "C69") (pin "1") (pinfunction "1_1") (pintype "passive"))
      (node (ref "C70") (pin "1") (pinfunction "1_1") (pintype "passive"))
      (node (ref "FB1") (pin "P$1") (pinfunction "1_P$1") (pintype "passive"))
      (node (ref "IC13") (pin "6") (pinfunction "VDD_6") (pintype "power_in"))
      (node (ref "IC14") (pin "6") (pinfunction "VCC_6") (pintype "passive"))
      (node (ref "IC15") (pin "1") (pinfunction "VDD_1") (pintype "power_in"))
      (node (ref "IC16") (pin "6") (pinfunction "VCC_6") (pintype "passive"))
      (node (ref "IC17") (pin "32") (pinfunction "IOVDD33-32_32") (pintype "power_in"))
      (node (ref "IC17") (pin "48") (pinfunction "IOVDD33-48_48") (pintype "power_in"))
      (node (ref "IC2") (pin "5") (pinfunction "VDD_5") (pintype "power_in"))
      (node (ref "IC5") (pin "4") (pinfunction "OUT_4") (pintype "passive"))
      (node (ref "IC6") (pin "6") (pinfunction "VCC_6") (pintype "passive"))
      (node (ref "IC7") (pin "6") (pinfunction "VCC_6") (pintype "passive"))
      (node (ref "IC8") (pin "1") (pinfunction "VDD-1_1") (pintype "power_in"))
      (node (ref "IC8") (pin "14") (pinfunction "VDD-14_14") (pintype "power_in"))
      (node (ref "IC8") (pin "27") (pinfunction "VDD-27_27") (pintype "power_in"))
      (node (ref "IC8") (pin "3") (pinfunction "VDDQ-3_3") (pintype "power_in"))
      (node (ref "IC8") (pin "43") (pinfunction "VDDQ-43_43") (pintype "power_in"))
      (node (ref "IC8") (pin "49") (pinfunction "VDDQ-49_49") (pintype "power_in"))
      (node (ref "IC8") (pin "9") (pinfunction "VDDQ-9_9") (pintype "power_in"))
      (node (ref "IC9") (pin "1") (pinfunction "A0_1") (pintype "input"))
      (node (ref "IC9") (pin "2") (pinfunction "A1_2") (pintype "input"))
      (node (ref "IC9") (pin "3") (pinfunction "A2_3") (pintype "input"))
      (node (ref "IC9") (pin "7") (pinfunction "WP_7") (pintype "input"))
      (node (ref "IC9") (pin "8") (pinfunction "VCC_8") (pintype "power_in"))
      (node (ref "J1") (pin "4") (pinfunction "VDD_4") (pintype "power_in"))
      (node (ref "L2") (pin "1") (pinfunction "1_1") (pintype "passive"))
      (node (ref "LCD1") (pin "4") (pinfunction "VDD_4") (pintype "power_in"))
      (node (ref "R1") (pin "1") (pinfunction "1_1") (pintype "passive"))
      (node (ref "R13") (pin "1") (pinfunction "1_1") (pintype "passive"))
      (node (ref "R15") (pin "1") (pinfunction "1_1") (pintype "passive"))
      (node (ref "R16") (pin "1") (pinfunction "1_1") (pintype "passive"))
      (node (ref "R17") (pin "1") (pinfunction "1_1") (pintype "passive"))
      (node (ref "R19") (pin "1") (pinfunction "1_1") (pintype "passive"))
      (node (ref "R25") (pin "1") (pinfunction "1_1") (pintype "passive"))
      (node (ref "R26") (pin "1") (pinfunction "1_1") (pintype "passive"))
      (node (ref "R27") (pin "1") (pinfunction "1_1") (pintype "passive"))
      (node (ref "R28") (pin "1") (pinfunction "1_1") (pintype "passive"))
      (node (ref "R31") (pin "2") (pinfunction "2_2") (pintype "passive"))
      (node (ref "R35") (pin "2") (pinfunction "2_2") (pintype "passive"))
      (node (ref "R40") (pin "2") (pinfunction "2_2") (pintype "passive"))
      (node (ref "R43") (pin "2") (pinfunction "2_2") (pintype "passive"))
      (node (ref "R47") (pin "1") (pinfunction "1_1") (pintype "passive"))
      (node (ref "R50") (pin "1") (pinfunction "1_1") (pintype "passive"))
      (node (ref "R51") (pin "1") (pinfunction "1_1") (pintype "passive"))
      (node (ref "R52") (pin "1") (pinfunction "1_1") (pintype "passive"))
      (node (ref "R54") (pin "1") (pinfunction "1_1") (pintype "passive"))
      (node (ref "R57") (pin "1") (pinfunction "1_1") (pintype "passive"))
      (node (ref "R58") (pin "1") (pinfunction "1_1") (pintype "passive"))
      (node (ref "R60") (pin "1") (pinfunction "1_1") (pintype "passive"))
      (node (ref "R9") (pin "1") (pinfunction "1_1") (pintype "passive"))
      (node (ref "X1") (pin "32") (pinfunction "1_32") (pintype "passive"))
      (node (ref "X2") (pin "16") (pinfunction "1_16") (pintype "passive"))
      (node (ref "X4") (pin "1") (pinfunction "1_1") (pintype "passive"))
      (node (ref "X4") (pin "2") (pinfunction "1_2") (pintype "passive"))
      (node (ref "X6") (pin "12") (pinfunction "YELLOW_A_12") (pintype "passive"))
      (node (ref "X6") (pin "9") (pinfunction "GREEN-A_9") (pintype "passive"))
    )
    (net (code "2") (name "+3V3(A)") (class "Default")
      (node (ref "C61") (pin "2") (pinfunction "2_2") (pintype "passive"))
      (node (ref "C63") (pin "2") (pinfunction "2_2") (pintype "passive"))
      (node (ref "C68") (pin "1") (pinfunction "1_1") (pintype "passive"))
      (node (ref "FB1") (pin "P$2") (pinfunction "2_P$2") (pintype "passive"))
      (node (ref "IC17") (pin "22") (pinfunction "AVDD33_22") (pintype "power_in"))
      (node (ref "X6") (pin "3") (pinfunction "CT_3") (pintype "input"))
      (node (ref "X6") (pin "6") (pinfunction "CR_6") (pintype "input"))
    )
    (net (code "3") (name "+5V") (class "Default")
      (node (ref "C1") (pin "1") (pinfunction "1_1") (pintype "passive"))
      (node (ref "C10") (pin "1") (pinfunction "+_1") (pintype "passive"))
      (node (ref "C11") (pin "1") (pinfunction "1_1") (pintype "passive"))
      (node (ref "C7") (pin "2") (pinfunction "2_2") (pintype "passive"))
      (node (ref "D1") (pin "C") (pinfunction "C_C") (pintype "passive"))
      (node (ref "IC1") (pin "6") (pinfunction "VCC_6") (pintype "passive"))
      (node (ref "IC10") (pin "5") (pinfunction "IN_5") (pintype "input"))
      (node (ref "IC3") (pin "8") (pinfunction "VSS_8") (pintype "passive"))
      (node (ref "IC5") (pin "3") (pinfunction "IN_3") (pintype "input"))
      (node (ref "VBUS") (pin "A") (pinfunction "A_A") (pintype "passive"))
      (node (ref "X1") (pin "3") (pinfunction "1_3") (pintype "passive"))
      (node (ref "X1") (pin "4") (pinfunction "1_4") (pintype "passive"))
      (node (ref "X2") (pin "5") (pinfunction "1_5") (pintype "passive"))
      (node (ref "X2") (pin "6") (pinfunction "1_6") (pintype "passive"))
    )
    (net (code "4") (name "+12V") (class "Default")
      (node (ref "X1") (pin "5") (pinfunction "1_5") (pintype "passive"))
      (node (ref "X1") (pin "6") (pinfunction "1_6") (pintype "passive"))
      (node (ref "X2") (pin "3") (pinfunction "1_3") (pintype "passive"))
      (node (ref "X2") (pin "4") (pinfunction "1_4") (pintype "passive"))
    )
    (net (code "5") (name "+VAUX") (class "Default")
      (node (ref "X1") (pin "34") (pinfunction "1_34") (pintype "passive"))
      (node (ref "X2") (pin "10") (pinfunction "1_10") (pintype "passive"))
    )
    (net (code "11") (name "BOOT0") (class "Default")
      (node (ref "IC4") (pin "166") (pinfunction "BOOT0_166") (pintype "input"))
      (node (ref "JP1") (pin "COM") (pinfunction "COM_COM") (pintype "passive"))
    )
    (net (code "12") (name "BYPASS_REG") (class "Default")
      (node (ref "IC4") (pin "48") (pinfunction "BYPASS_REG_48") (pintype "input"))
      (node (ref "R12") (pin "2") (pinfunction "2_2") (pintype "passive"))
    )
    (net (code "13") (name "DAC_OUT1") (class "Default")
      (node (ref "C52") (pin "2") (pinfunction "2_2") (pintype "passive"))
      (node (ref "IC4") (pin "50") (pinfunction "PA4_50") (pintype "bidirectional"))
    )
    (net (code "14") (name "DBGACK") (class "Default")
      (node (ref "R24") (pin "1") (pinfunction "1_1") (pintype "passive"))
      (node (ref "X4") (pin "19") (pinfunction "1_19") (pintype "passive"))
    )
    (net (code "15") (name "DBGRQ") (class "Default")
      (node (ref "R23") (pin "1") (pinfunction "1_1") (pintype "passive"))
      (node (ref "X4") (pin "17") (pinfunction "1_17") (pintype "passive"))
    )
    (net (code "16") (name "DIN1") (class "Default")
      (node (ref "IC4") (pin "7") (pinfunction "PI8_7") (pintype "bidirectional"))
      (node (ref "R4") (pin "2") (pinfunction "2_2") (pintype "passive"))
    )
    (net (code "17") (name "DIN2") (class "Default")
      (node (ref "IC4") (pin "8") (pinfunction "PC13_8") (pintype "bidirectional"))
      (node (ref "R8") (pin "2") (pinfunction "2_2") (pintype "passive"))
    )
    (net (code "18") (name "DOUT1") (class "Default")
      (node (ref "IC3") (pin "2") (pinfunction "IN1_2") (pintype "input"))
      (node (ref "IC4") (pin "9") (pinfunction "PC14_9") (pintype "bidirectional"))
    )
    (net (code "19") (name "DOUT2") (class "Default")
      (node (ref "IC3") (pin "3") (pinfunction "IN2_3") (pintype "input"))
      (node (ref "IC4") (pin "10") (pinfunction "PC15_10") (pintype "bidirectional"))
    )
    (net (code "20") (name "ENC_A") (class "Default")
      (node (ref "C5") (pin "2") (pinfunction "2_2") (pintype "passive"))
      (node (ref "IC4") (pin "119") (pinfunction "PC6_119") (pintype "bidirectional"))
      (node (ref "R5") (pin "1") (pinfunction "1_1") (pintype "passive"))
    )
    (net (code "21") (name "ENC_B") (class "Default")
      (node (ref "C6") (pin "1") (pinfunction "1_1") (pintype "passive"))
      (node (ref "IC4") (pin "120") (pinfunction "PC7_120") (pintype "bidirectional"))
      (node (ref "R10") (pin "1") (pinfunction "1_1") (pintype "passive"))
    )
    (net (code "22") (name "ENC_SW") (class "Default")
      (node (ref "C2") (pin "2") (pinfunction "2_2") (pintype "passive"))
      (node (ref "IC4") (pin "173") (pinfunction "PI4_173") (pintype "bidirectional"))
      (node (ref "SW1") (pin "E") (pinfunction "2_E") (pintype "passive"))
    )
    (net (code "23") (name "ETH_COL") (class "Default")
      (node (ref "IC4") (pin "47") (pinfunction "PA3_47") (pintype "bidirectional"))
      (node (ref "RN2") (pin "2") (pinfunction "1_2") (pintype "passive"))
    )
    (net (code "24") (name "ETH_CRS") (class "Default")
      (node (ref "IC4") (pin "40") (pinfunction "PA0_40") (pintype "bidirectional"))
      (node (ref "JP5") (pin "1") (pinfunction "1_1") (pintype "passive"))
      (node (ref "RN1") (pin "4") (pinfunction "1_4") (pintype "passive"))
    )
    (net (code "25") (name "ETH_MDC") (class "Default")
      (node (ref "IC17") (pin "31") (pinfunction "MDC_31") (pintype "input"))
      (node (ref "IC4") (pin "33") (pinfunction "PC1_33") (pintype "bidirectional"))
    )
    (net (code "26") (name "ETH_MDIO") (class "Default")
      (node (ref "IC17") (pin "30") (pinfunction "MDIO_30") (pintype "bidirectional"))
      (node (ref "IC4") (pin "42") (pinfunction "PA2_42") (pintype "bidirectional"))
      (node (ref "R43") (pin "1") (pinfunction "1_1") (pintype "passive"))
    )
    (net (code "27") (name "ETH_RXD0") (class "Default")
      (node (ref "IC4") (pin "54") (pinfunction "PC4_54") (pintype "bidirectional"))
      (node (ref "RN2") (pin "3") (pinfunction "1_3") (pintype "passive"))
    )
    (net (code "28") (name "ETH_RXD1") (class "Default")
      (node (ref "IC4") (pin "55") (pinfunction "PC5_55") (pintype "bidirectional"))
      (node (ref "RN2") (pin "4") (pinfunction "1_4") (pintype "passive"))
    )
    (net (code "29") (name "ETH_RXD2") (class "Default")
      (node (ref "IC4") (pin "83") (pinfunction "PH6_83") (pintype "bidirectional"))
      (node (ref "RN3") (pin "1") (pinfunction "1_1") (pintype "passive"))
    )
    (net (code "30") (name "ETH_RXD3") (class "Default")
      (node (ref "IC4") (pin "84") (pinfunction "PH7_84") (pintype "bidirectional"))
      (node (ref "RN3") (pin "2") (pinfunction "1_2") (pintype "passive"))
    )
    (net (code "31") (name "ETH_RX_CLK") (class "Default")
      (node (ref "IC4") (pin "41") (pinfunction "PA1_41") (pintype "bidirectional"))
      (node (ref "RN1") (pin "2") (pinfunction "1_2") (pintype "passive"))
    )
    (net (code "32") (name "ETH_RX_DV") (class "Default")
      (node (ref "IC4") (pin "53") (pinfunction "PA7_53") (pintype "bidirectional"))
      (node (ref "RN1") (pin "3") (pinfunction "1_3") (pintype "passive"))
    )
    (net (code "33") (name "ETH_TXD0") (class "Default")
      (node (ref "IC4") (pin "85") (pinfunction "PB12_85") (pintype "bidirectional"))
      (node (ref "RN4") (pin "1") (pinfunction "1_1") (pintype "passive"))
    )
    (net (code "34") (name "ETH_TXD1") (class "Default")
      (node (ref "IC4") (pin "86") (pinfunction "PB13_86") (pintype "bidirectional"))
      (node (ref "RN4") (pin "2") (pinfunction "1_2") (pintype "passive"))
    )
    (net (code "35") (name "ETH_TXD2") (class "Default")
      (node (ref "IC4") (pin "34") (pinfunction "PC2_34") (pintype "bidirectional"))
      (node (ref "RN4") (pin "3") (pinfunction "1_3") (pintype "passive"))
    )
    (net (code "36") (name "ETH_TXD3") (class "Default")
      (node (ref "IC4") (pin "167") (pinfunction "PB8_167") (pintype "bidirectional"))
      (node (ref "RN4") (pin "4") (pinfunction "1_4") (pintype "passive"))
    )
    (net (code "37") (name "ETH_TX_CLK") (class "Default")
      (node (ref "IC4") (pin "35") (pinfunction "PC3_35") (pintype "bidirectional"))
      (node (ref "RN3") (pin "3") (pinfunction "1_3") (pintype "passive"))
    )
    (net (code "38") (name "ETH_TX_EN") (class "Default")
      (node (ref "IC4") (pin "80") (pinfunction "PB11_80") (pintype "bidirectional"))
      (node (ref "RN3") (pin "4") (pinfunction "1_4") (pintype "passive"))
    )
    (net (code "39") (name "FMC_A0") (class "Default")
      (node (ref "IC4") (pin "16") (pinfunction "PF0_16") (pintype "bidirectional"))
      (node (ref "IC8") (pin "23") (pinfunction "A0_23") (pintype "input"))
    )
    (net (code "40") (name "FMC_A1") (class "Default")
      (node (ref "IC4") (pin "17") (pinfunction "PF1_17") (pintype "bidirectional"))
      (node (ref "IC8") (pin "24") (pinfunction "A1_24") (pintype "input"))
    )
    (net (code "41") (name "FMC_A2") (class "Default")
      (node (ref "IC4") (pin "18") (pinfunction "PF2_18") (pintype "bidirectional"))
      (node (ref "IC8") (pin "25") (pinfunction "A2_25") (pintype "input"))
    )
    (net (code "42") (name "FMC_A3") (class "Default")
      (node (ref "IC4") (pin "19") (pinfunction "PF3_19") (pintype "bidirectional"))
      (node (ref "IC8") (pin "26") (pinfunction "A3_26") (pintype "input"))
    )
    (net (code "43") (name "FMC_A4") (class "Default")
      (node (ref "IC4") (pin "20") (pinfunction "PF4_20") (pintype "bidirectional"))
      (node (ref "IC8") (pin "29") (pinfunction "A4_29") (pintype "input"))
    )
    (net (code "44") (name "FMC_A5") (class "Default")
      (node (ref "IC4") (pin "21") (pinfunction "PF5_21") (pintype "bidirectional"))
      (node (ref "IC8") (pin "30") (pinfunction "A5_30") (pintype "input"))
    )
    (net (code "45") (name "FMC_A6") (class "Default")
      (node (ref "IC4") (pin "60") (pinfunction "PF12_60") (pintype "bidirectional"))
      (node (ref "IC8") (pin "31") (pinfunction "A6_31") (pintype "input"))
    )
    (net (code "46") (name "FMC_A7") (class "Default")
      (node (ref "IC4") (pin "63") (pinfunction "PF13_63") (pintype "bidirectional"))
      (node (ref "IC8") (pin "32") (pinfunction "A7_32") (pintype "input"))
    )
    (net (code "47") (name "FMC_A8") (class "Default")
      (node (ref "IC4") (pin "64") (pinfunction "PF14_64") (pintype "bidirectional"))
      (node (ref "IC8") (pin "33") (pinfunction "A8_33") (pintype "input"))
    )
    (net (code "48") (name "FMC_A9") (class "Default")
      (node (ref "IC4") (pin "65") (pinfunction "PF15_65") (pintype "bidirectional"))
      (node (ref "IC8") (pin "34") (pinfunction "A9_34") (pintype "input"))
    )
    (net (code "49") (name "FMC_A10") (class "Default")
      (node (ref "IC4") (pin "66") (pinfunction "PG0_66") (pintype "bidirectional"))
      (node (ref "IC8") (pin "22") (pinfunction "A10/AP_22") (pintype "input"))
    )
    (net (code "50") (name "FMC_A11") (class "Default")
      (node (ref "IC4") (pin "67") (pinfunction "PG1_67") (pintype "bidirectional"))
      (node (ref "IC8") (pin "35") (pinfunction "A11_35") (pintype "input"))
    )
    (net (code "51") (name "FMC_BA0") (class "Default")
      (node (ref "IC4") (pin "112") (pinfunction "PG4_112") (pintype "bidirectional"))
      (node (ref "IC8") (pin "20") (pinfunction "BA0_20") (pintype "input"))
    )
    (net (code "52") (name "FMC_BA1") (class "Default")
      (node (ref "IC4") (pin "113") (pinfunction "PG5_113") (pintype "bidirectional"))
      (node (ref "IC8") (pin "21") (pinfunction "BA1_21") (pintype "input"))
    )
    (net (code "53") (name "FMC_D0") (class "Default")
      (node (ref "IC4") (pin "97") (pinfunction "PD14_97") (pintype "bidirectional"))
      (node (ref "IC8") (pin "2") (pinfunction "DQ0_2") (pintype "bidirectional"))
    )
    (net (code "54") (name "FMC_D1") (class "Default")
      (node (ref "IC4") (pin "98") (pinfunction "PD15_98") (pintype "bidirectional"))
      (node (ref "IC8") (pin "4") (pinfunction "DQ1_4") (pintype "bidirectional"))
    )
    (net (code "55") (name "FMC_D2") (class "Default")
      (node (ref "IC4") (pin "142") (pinfunction "PD0_142") (pintype "bidirectional"))
      (node (ref "IC8") (pin "5") (pinfunction "DQ2_5") (pintype "bidirectional"))
    )
    (net (code "56") (name "FMC_D3") (class "Default")
      (node (ref "IC4") (pin "143") (pinfunction "PD1_143") (pintype "bidirectional"))
      (node (ref "IC8") (pin "7") (pinfunction "DQ3_7") (pintype "bidirectional"))
    )
    (net (code "57") (name "FMC_D4") (class "Default")
      (node (ref "IC4") (pin "68") (pinfunction "PE7_68") (pintype "bidirectional"))
      (node (ref "IC8") (pin "8") (pinfunction "DQ4_8") (pintype "bidirectional"))
    )
    (net (code "58") (name "FMC_D5") (class "Default")
      (node (ref "IC4") (pin "69") (pinfunction "PE8_69") (pintype "bidirectional"))
      (node (ref "IC8") (pin "10") (pinfunction "DQ5_10") (pintype "bidirectional"))
    )
    (net (code "59") (name "FMC_D6") (class "Default")
      (node (ref "IC4") (pin "70") (pinfunction "PE9_70") (pintype "bidirectional"))
      (node (ref "IC8") (pin "11") (pinfunction "DQ6_11") (pintype "bidirectional"))
    )
    (net (code "60") (name "FMC_D7") (class "Default")
      (node (ref "IC4") (pin "73") (pinfunction "PE10_73") (pintype "bidirectional"))
      (node (ref "IC8") (pin "13") (pinfunction "DQ7_13") (pintype "bidirectional"))
    )
    (net (code "61") (name "FMC_D8") (class "Default")
      (node (ref "IC4") (pin "74") (pinfunction "PE11_74") (pintype "bidirectional"))
      (node (ref "IC8") (pin "42") (pinfunction "DQ8_42") (pintype "bidirectional"))
    )
    (net (code "62") (name "FMC_D9") (class "Default")
      (node (ref "IC4") (pin "75") (pinfunction "PE12_75") (pintype "bidirectional"))
      (node (ref "IC8") (pin "44") (pinfunction "DQ9_44") (pintype "bidirectional"))
    )
    (net (code "63") (name "FMC_D10") (class "Default")
      (node (ref "IC4") (pin "76") (pinfunction "PE13_76") (pintype "bidirectional"))
      (node (ref "IC8") (pin "45") (pinfunction "DQ10_45") (pintype "bidirectional"))
    )
    (net (code "64") (name "FMC_D11") (class "Default")
      (node (ref "IC4") (pin "77") (pinfunction "PE14_77") (pintype "bidirectional"))
      (node (ref "IC8") (pin "47") (pinfunction "DQ11_47") (pintype "bidirectional"))
    )
    (net (code "65") (name "FMC_D12") (class "Default")
      (node (ref "IC4") (pin "78") (pinfunction "PE15_78") (pintype "bidirectional"))
      (node (ref "IC8") (pin "48") (pinfunction "DQ12_48") (pintype "bidirectional"))
    )
    (net (code "66") (name "FMC_D13") (class "Default")
      (node (ref "IC4") (pin "89") (pinfunction "PD8_89") (pintype "bidirectional"))
      (node (ref "IC8") (pin "50") (pinfunction "DQ13_50") (pintype "bidirectional"))
    )
    (net (code "67") (name "FMC_D14") (class "Default")
      (node (ref "IC4") (pin "90") (pinfunction "PD9_90") (pintype "bidirectional"))
      (node (ref "IC8") (pin "51") (pinfunction "DQ14_51") (pintype "bidirectional"))
    )
    (net (code "68") (name "FMC_D15") (class "Default")
      (node (ref "IC4") (pin "91") (pinfunction "PD10_91") (pintype "bidirectional"))
      (node (ref "IC8") (pin "53") (pinfunction "DQ15_53") (pintype "bidirectional"))
    )
    (net (code "69") (name "FMC_NBL0") (class "Default")
      (node (ref "IC4") (pin "169") (pinfunction "PE0_169") (pintype "bidirectional"))
      (node (ref "IC8") (pin "15") (pinfunction "LDQM_15") (pintype "input"))
    )
    (net (code "70") (name "FMC_NBL1") (class "Default")
      (node (ref "IC4") (pin "170") (pinfunction "PE1_170") (pintype "bidirectional"))
      (node (ref "IC8") (pin "39") (pinfunction "UDQM_39") (pintype "input"))
    )
    (net (code "71") (name "FMC_SDCKE0") (class "Default")
      (node (ref "IC4") (pin "43") (pinfunction "PH2_43") (pintype "bidirectional"))
      (node (ref "IC8") (pin "37") (pinfunction "CKE_37") (pintype "input"))
    )
    (net (code "72") (name "FMC_SDCLK") (class "Default")
      (node (ref "IC4") (pin "116") (pinfunction "PG8_116") (pintype "bidirectional"))
      (node (ref "IC8") (pin "38") (pinfunction "CLK_38") (pintype "input"))
    )
    (net (code "73") (name "FMC_SDNCAS") (class "Default")
      (node (ref "IC4") (pin "160") (pinfunction "PG15_160") (pintype "bidirectional"))
      (node (ref "IC8") (pin "17") (pinfunction "~{CAS}_17") (pintype "input"))
    )
    (net (code "74") (name "FMC_SDNE0") (class "Default")
      (node (ref "IC4") (pin "44") (pinfunction "PH3_44") (pintype "bidirectional"))
      (node (ref "IC8") (pin "19") (pinfunction "~{CS}_19") (pintype "input"))
      (node (ref "R25") (pin "2") (pinfunction "2_2") (pintype "passive"))
    )
    (net (code "75") (name "FMC_SDNRAS") (class "Default")
      (node (ref "IC4") (pin "59") (pinfunction "PF11_59") (pintype "bidirectional"))
      (node (ref "IC8") (pin "18") (pinfunction "~{RAS}_18") (pintype "input"))
    )
    (net (code "76") (name "FMC_SDNWE") (class "Default")
      (node (ref "IC4") (pin "46") (pinfunction "PH5_46") (pintype "bidirectional"))
      (node (ref "IC8") (pin "16") (pinfunction "~{WE}_16") (pintype "input"))
    )
    (net (code "77") (name "GND") (class "Default")
      (node (ref "B1") (pin "1") (pinfunction "-_1") (pintype "passive"))
      (node (ref "B1") (pin "3") (pinfunction "-_3") (pintype "passive"))
      (node (ref "C1") (pin "2") (pinfunction "2_2") (pintype "passive"))
      (node (ref "C10") (pin "2") (pinfunction "-_2") (pintype "passive"))
      (node (ref "C11") (pin "2") (pinfunction "2_2") (pintype "passive"))
      (node (ref "C12") (pin "-") (pinfunction "-_-") (pintype "passive"))
      (node (ref "C13") (pin "2") (pinfunction "2_2") (pintype "passive"))
      (node (ref "C14") (pin "2") (pinfunction "2_2") (pintype "passive"))
      (node (ref "C15") (pin "2") (pinfunction "2_2") (pintype "passive"))
      (node (ref "C16") (pin "2") (pinfunction "2_2") (pintype "passive"))
      (node (ref "C17") (pin "2") (pinfunction "2_2") (pintype "passive"))
      (node (ref "C18") (pin "2") (pinfunction "2_2") (pintype "passive"))
      (node (ref "C19") (pin "-") (pinfunction "-_-") (pintype "passive"))
      (node (ref "C2") (pin "1") (pinfunction "1_1") (pintype "passive"))
      (node (ref "C20") (pin "2") (pinfunction "2_2") (pintype "passive"))
      (node (ref "C21") (pin "2") (pinfunction "2_2") (pintype "passive"))
      (node (ref "C22") (pin "2") (pinfunction "2_2") (pintype "passive"))
      (node (ref "C23") (pin "2") (pinfunction "2_2") (pintype "passive"))
      (node (ref "C24") (pin "2") (pinfunction "2_2") (pintype "passive"))
      (node (ref "C25") (pin "2") (pinfunction "2_2") (pintype "passive"))
      (node (ref "C26") (pin "2") (pinfunction "2_2") (pintype "passive"))
      (node (ref "C27") (pin "2") (pinfunction "2_2") (pintype "passive"))
      (node (ref "C28") (pin "2") (pinfunction "2_2") (pintype "passive"))
      (node (ref "C29") (pin "2") (pinfunction "2_2") (pintype "passive"))
      (node (ref "C3") (pin "1") (pinfunction "1_1") (pintype "passive"))
      (node (ref "C30") (pin "2") (pinfunction "2_2") (pintype "passive"))
      (node (ref "C31") (pin "2") (pinfunction "2_2") (pintype "passive"))
      (node (ref "C32") (pin "2") (pinfunction "2_2") (pintype "passive"))
      (node (ref "C33") (pin "2") (pinfunction "2_2") (pintype "passive"))
      (node (ref "C34") (pin "2") (pinfunction "2_2") (pintype "passive"))
      (node (ref "C35") (pin "2") (pinfunction "2_2") (pintype "passive"))
      (node (ref "C36") (pin "2") (pinfunction "2_2") (pintype "passive"))
      (node (ref "C37") (pin "2") (pinfunction "2_2") (pintype "passive"))
      (node (ref "C38") (pin "1") (pinfunction "1_1") (pintype "passive"))
      (node (ref "C39") (pin "2") (pinfunction "2_2") (pintype "passive"))
      (node (ref "C4") (pin "2") (pinfunction "2_2") (pintype "passive"))
      (node (ref "C40") (pin "2") (pinfunction "2_2") (pintype "passive"))
      (node (ref "C41") (pin "2") (pinfunction "2_2") (pintype "passive"))
      (node (ref "C42") (pin "2") (pinfunction "2_2") (pintype "passive"))
      (node (ref "C43") (pin "2") (pinfunction "2_2") (pintype "passive"))
      (node (ref "C44") (pin "2") (pinfunction "2_2") (pintype "passive"))
      (node (ref "C45") (pin "2") (pinfunction "2_2") (pintype "passive"))
      (node (ref "C46") (pin "2") (pinfunction "2_2") (pintype "passive"))
      (node (ref "C47") (pin "-") (pinfunction "-_-") (pintype "passive"))
      (node (ref "C48") (pin "2") (pinfunction "2_2") (pintype "passive"))
      (node (ref "C49") (pin "1") (pinfunction "1_1") (pintype "passive"))
      (node (ref "C5") (pin "1") (pinfunction "1_1") (pintype "passive"))
      (node (ref "C50") (pin "1") (pinfunction "1_1") (pintype "passive"))
      (node (ref "C51") (pin "2") (pinfunction "2_2") (pintype "passive"))
      (node (ref "C53") (pin "1") (pinfunction "1_1") (pintype "passive"))
      (node (ref "C54") (pin "1") (pinfunction "1_1") (pintype "passive"))
      (node (ref "C55") (pin "1") (pinfunction "1_1") (pintype "passive"))
      (node (ref "C56") (pin "1") (pinfunction "1_1") (pintype "passive"))
      (node (ref "C57") (pin "2") (pinfunction "2_2") (pintype "passive"))
      (node (ref "C58") (pin "2") (pinfunction "2_2") (pintype "passive"))
      (node (ref "C59") (pin "2") (pinfunction "2_2") (pintype "passive"))
      (node (ref "C6") (pin "2") (pinfunction "2_2") (pintype "passive"))
      (node (ref "C60") (pin "2") (pinfunction "2_2") (pintype "passive"))
      (node (ref "C61") (pin "1") (pinfunction "1_1") (pintype "passive"))
      (node (ref "C62") (pin "2") (pinfunction "2_2") (pintype "passive"))
      (node (ref "C63") (pin "1") (pinfunction "1_1") (pintype "passive"))
      (node (ref "C64") (pin "2") (pinfunction "2_2") (pintype "passive"))
      (node (ref "C65") (pin "2") (pinfunction "2_2") (pintype "passive"))
      (node (ref "C66") (pin "-") (pinfunction "-_-") (pintype "passive"))
      (node (ref "C67") (pin "2") (pinfunction "2_2") (pintype "passive"))
      (node (ref "C68") (pin "2") (pinfunction "2_2") (pintype "passive"))
      (node (ref "C69") (pin "2") (pinfunction "2_2") (pintype "passive"))
      (node (ref "C7") (pin "1") (pinfunction "1_1") (pintype "passive"))
      (node (ref "C70") (pin "2") (pinfunction "2_2") (pintype "passive"))
      (node (ref "C8") (pin "1") (pinfunction "1_1") (pintype "passive"))
      (node (ref "C9") (pin "1") (pinfunction "1_1") (pintype "passive"))
      (node (ref "D1") (pin "A") (pinfunction "A_A") (pintype "passive"))
      (node (ref "IC1") (pin "3") (pinfunction "GND_3") (pintype "power_in"))
      (node (ref "IC10") (pin "2") (pinfunction "GND_2") (pintype "power_in"))
      (node (ref "IC11") (pin "2") (pinfunction "GND_2") (pintype "power_in"))
      (node (ref "IC12") (pin "3") (pinfunction "GND_3") (pintype "power_in"))
      (node (ref "IC13") (pin "7") (pinfunction "GND_7") (pintype "passive"))
      (node (ref "IC13") (pin "TP") (pinfunction "TP_TP") (pintype "passive"))
      (node (ref "IC14") (pin "3") (pinfunction "GND_3") (pintype "power_in"))
      (node (ref "IC15") (pin "14") (pinfunction "SX+_14") (pintype "bidirectional"))
      (node (ref "IC15") (pin "17") (pinfunction "5WSX-_17") (pintype "input"))
      (node (ref "IC15") (pin "2") (pinfunction "M1_2") (pintype "bidirectional"))
      (node (ref "IC15") (pin "20") (pinfunction "VSS_20") (pintype "power_in"))
      (node (ref "IC15") (pin "3") (pinfunction "SY-_3") (pintype "bidirectional"))
      (node (ref "IC15") (pin "4") (pinfunction "M2_4") (pintype "input"))
      (node (ref "IC15") (pin "7") (pinfunction "SY+_7") (pintype "bidirectional"))
      (node (ref "IC16") (pin "3") (pinfunction "GND_3") (pintype "power_in"))
      (node (ref "IC17") (pin "15") (pinfunction "AGND-15_15") (pintype "power_in"))
      (node (ref "IC17") (pin "19") (pinfunction "AGND-19_19") (pintype "power_in"))
      (node (ref "IC17") (pin "35") (pinfunction "IOGND-35_35") (pintype "power_in"))
      (node (ref "IC17") (pin "36") (pinfunction "DGND_36") (pintype "power_in"))
      (node (ref "IC17") (pin "47") (pinfunction "IOGND-47_47") (pintype "power_in"))
      (node (ref "IC2") (pin "2") (pinfunction "VSS_2") (pintype "power_in"))
      (node (ref "IC3") (pin "6") (pinfunction "GND_6") (pintype "passive"))
      (node (ref "IC4") (pin "103") (pinfunction "VSSDSI_2_103") (pintype "power_in"))
      (node (ref "IC4") (pin "109") (pinfunction "VSSDSI_109") (pintype "power_in"))
      (node (ref "IC4") (pin "117") (pinfunction "VSS_7_117") (pintype "power_in"))
      (node (ref "IC4") (pin "130") (pinfunction "VSS_8_130") (pintype "power_in"))
      (node (ref "IC4") (pin "135") (pinfunction "VSS_9_135") (pintype "power_in"))
      (node (ref "IC4") (pin "14") (pinfunction "VSS_2_14") (pintype "power_in"))
      (node (ref "IC4") (pin "148") (pinfunction "VSS_10_148") (pintype "power_in"))
      (node (ref "IC4") (pin "158") (pinfunction "VSS_158") (pintype "power_in"))
      (node (ref "IC4") (pin "22") (pinfunction "VSS_3_22") (pintype "power_in"))
      (node (ref "IC4") (pin "37") (pinfunction "VSSA_37") (pintype "power_in"))
      (node (ref "IC4") (pin "61") (pinfunction "VSS_4_61") (pintype "power_in"))
      (node (ref "IC4") (pin "71") (pinfunction "VSS_5_71") (pintype "power_in"))
      (node (ref "IC4") (pin "95") (pinfunction "VSS_6_95") (pintype "power_in"))
      (node (ref "IC5") (pin "1") (pinfunction "ADJ_1") (pintype "input"))
      (node (ref "IC6") (pin "3") (pinfunction "GND_3") (pintype "power_in"))
      (node (ref "IC7") (pin "3") (pinfunction "GND_3") (pintype "power_in"))
      (node (ref "IC8") (pin "12") (pinfunction "GNDQ-12_12") (pintype "power_in"))
      (node (ref "IC8") (pin "28") (pinfunction "GND-28_28") (pintype "power_in"))
      (node (ref "IC8") (pin "41") (pinfunction "GND_41") (pintype "power_in"))
      (node (ref "IC8") (pin "46") (pinfunction "GNDQ-46_46") (pintype "power_in"))
      (node (ref "IC8") (pin "52") (pinfunction "GNDQ-52_52") (pintype "power_in"))
      (node (ref "IC8") (pin "54") (pinfunction "GND-54_54") (pintype "power_in"))
      (node (ref "IC8") (pin "6") (pinfunction "GNDQ-6_6") (pintype "power_in"))
      (node (ref "IC9") (pin "4") (pinfunction "GND_4") (pintype "passive"))
      (node (ref "J1") (pin "6") (pinfunction "VSS_6") (pintype "power_in"))
      (node (ref "J1") (pin "S") (pinfunction "SH_S") (pintype "passive"))
      (node (ref "J1") (pin "SW2") (pinfunction "SW2_SW2") (pintype "passive"))
      (node (ref "JP1") (pin "NC") (pinfunction "NC_NC") (pintype "passive"))
      (node (ref "JP4") (pin "NO") (pinfunction "NO_NO") (pintype "passive"))
      (node (ref "LCD1") (pin "13") (pinfunction "G0_13") (pintype "input"))
      (node (ref "LCD1") (pin "14") (pinfunction "G1_14") (pintype "input"))
      (node (ref "LCD1") (pin "21") (pinfunction "B0_21") (pintype "input"))
      (node (ref "LCD1") (pin "22") (pinfunction "B1_22") (pintype "input"))
      (node (ref "LCD1") (pin "29") (pinfunction "GND-29_29") (pintype "power_in"))
      (node (ref "LCD1") (pin "3") (pinfunction "GND-3_3") (pintype "power_in"))
      (node (ref "LCD1") (pin "5") (pinfunction "R0_5") (pintype "input"))
      (node (ref "LCD1") (pin "6") (pinfunction "R1_6") (pintype "input"))
      (node (ref "Q1") (pin "E") (pinfunction "E_E") (pintype "passive"))
      (node (ref "R12") (pin "1") (pinfunction "1_1") (pintype "passive"))
      (node (ref "R22") (pin "2") (pinfunction "2_2") (pintype "passive"))
      (node (ref "R23") (pin "2") (pinfunction "2_2") (pintype "passive"))
      (node (ref "R24") (pin "2") (pinfunction "2_2") (pintype "passive"))
      (node (ref "R30") (pin "2") (pinfunction "2_2") (pintype "passive"))
      (node (ref "R46") (pin "1") (pinfunction "1_1") (pintype "passive"))
      (node (ref "R49") (pin "1") (pinfunction "1_1") (pintype "passive"))
      (node (ref "R59") (pin "1") (pinfunction "1_1") (pintype "passive"))
      (node (ref "SW1") (pin "C") (pinfunction "C_C") (pintype "passive"))
      (node (ref "SW1") (pin "D") (pinfunction "1_D") (pintype "passive"))
      (node (ref "SW1") (pin "GND1") (pinfunction "C_GND1") (pintype "passive"))
      (node (ref "SW1") (pin "GND2") (pinfunction "C_GND2") (pintype "passive"))
      (node (ref "SW2") (pin "2") (pinfunction "2_2") (pintype "passive"))
      (node (ref "SW2") (pin "3") (pinfunction "GND_3") (pintype "power_in"))
      (node (ref "SW2") (pin "4") (pinfunction "GND_4") (pintype "power_in"))
      (node (ref "TOUCH") (pin "C") (pinfunction "C_C") (pintype "passive"))
      (node (ref "X1") (pin "1") (pinfunction "1_1") (pintype "passive"))
      (node (ref "X1") (pin "2") (pinfunction "1_2") (pintype "passive"))
      (node (ref "X1") (pin "21") (pinfunction "1_21") (pintype "passive"))
      (node (ref "X1") (pin "22") (pinfunction "1_22") (pintype "passive"))
      (node (ref "X1") (pin "35") (pinfunction "1_35") (pintype "passive"))
      (node (ref "X1") (pin "36") (pinfunction "1_36") (pintype "passive"))
      (node (ref "X1") (pin "40") (pinfunction "1_40") (pintype "passive"))
      (node (ref "X1") (pin "7") (pinfunction "1_7") (pintype "passive"))
      (node (ref "X1") (pin "8") (pinfunction "1_8") (pintype "passive"))
      (node (ref "X2") (pin "7") (pinfunction "1_7") (pintype "passive"))
      (node (ref "X2") (pin "8") (pinfunction "1_8") (pintype "passive"))
      (node (ref "X2") (pin "9") (pinfunction "1_9") (pintype "passive"))
      (node (ref "X3") (pin "3") (pinfunction "1_3") (pintype "passive"))
      (node (ref "X4") (pin "10") (pinfunction "1_10") (pintype "passive"))
      (node (ref "X4") (pin "12") (pinfunction "1_12") (pintype "passive"))
      (node (ref "X4") (pin "14") (pinfunction "1_14") (pintype "passive"))
      (node (ref "X4") (pin "16") (pinfunction "1_16") (pintype "passive"))
      (node (ref "X4") (pin "18") (pinfunction "1_18") (pintype "passive"))
      (node (ref "X4") (pin "20") (pinfunction "1_20") (pintype "passive"))
      (node (ref "X4") (pin "4") (pinfunction "1_4") (pintype "passive"))
      (node (ref "X4") (pin "6") (pinfunction "1_6") (pintype "passive"))
      (node (ref "X4") (pin "8") (pinfunction "1_8") (pintype "passive"))
      (node (ref "X6") (pin "4") (pinfunction "GND_4") (pintype "passive"))
      (node (ref "X6") (pin "5") (pinfunction "GND_5") (pintype "passive"))
      (node (ref "ZD1") (pin "A") (pinfunction "A_A") (pintype "passive"))
      (node (ref "ZD2") (pin "A") (pinfunction "A_A") (pintype "passive"))
    )
    (net (code "78") (name "I2C1_SCL") (class "Default")
      (node (ref "IC15") (pin "11") (pinfunction "SCK/SCL/TX_11") (pintype "bidirectional"))
      (node (ref "IC4") (pin "164") (pinfunction "PB6_164") (pintype "bidirectional"))
      (node (ref "IC9") (pin "5") (pinfunction "SDA_5") (pintype "bidirectional"))
      (node (ref "R15") (pin "2") (pinfunction "2_2") (pintype "passive"))
      (node (ref "X1") (pin "28") (pinfunction "1_28") (pintype "passive"))
      (node (ref "X2") (pin "13") (pinfunction "1_13") (pintype "passive"))
    )
    (net (code "79") (name "I2C1_SDA") (class "Default")
      (node (ref "IC15") (pin "13") (pinfunction "SDI/SDA/RX_13") (pintype "bidirectional"))
      (node (ref "IC4") (pin "165") (pinfunction "PB7_165") (pintype "bidirectional"))
      (node (ref "IC9") (pin "6") (pinfunction "SCL_6") (pintype "bidirectional"))
      (node (ref "R16") (pin "2") (pinfunction "2_2") (pintype "passive"))
      (node (ref "X1") (pin "30") (pinfunction "1_30") (pintype "passive"))
      (node (ref "X2") (pin "14") (pinfunction "1_14") (pintype "passive"))
    )
    (net (code "80") (name "IRQ_TOUCH") (class "Default")
      (node (ref "IC15") (pin "9") (pinfunction "SDO_9") (pintype "bidirectional"))
      (node (ref "IC4") (pin "151") (pinfunction "PD7_151") (pintype "bidirectional"))
    )
    (net (code "81") (name "LCD_DISP") (class "Default")
      (node (ref "LCD1") (pin "31") (pinfunction "DISP_31") (pintype "input"))
      (node (ref "R35") (pin "1") (pinfunction "1_1") (pintype "passive"))
    )
    (net (code "82") (name "LED_ACT") (class "Default")
      (node (ref "IC17") (pin "26") (pinfunction "AN_EN(LED_ACT/COL)_26") (pintype "output"))
      (node (ref "R47") (pin "2") (pinfunction "2_2") (pintype "passive"))
      (node (ref "R55") (pin "2") (pinfunction "2_2") (pintype "passive"))
    )
    (net (code "83") (name "LED_LINK") (class "Default")
      (node (ref "IC17") (pin "28") (pinfunction "AN_0(LED_LINK)_28") (pintype "output"))
      (node (ref "R54") (pin "2") (pinfunction "2_2") (pintype "passive"))
      (node (ref "R56") (pin "2") (pinfunction "2_2") (pintype "passive"))
    )
    (net (code "84") (name "LED_SPEED") (class "Default")
      (node (ref "IC17") (pin "27") (pinfunction "AN_1(LED_SPEED)_27") (pintype "output"))
      (node (ref "R52") (pin "2") (pinfunction "2_2") (pintype "passive"))
      (node (ref "SPEED") (pin "C") (pinfunction "C_C") (pintype "passive"))
    )
    (net (code "85") (name "LTDC_B2") (class "Default")
      (node (ref "IC4") (pin "150") (pinfunction "PD6_150") (pintype "bidirectional"))
      (node (ref "LCD1") (pin "23") (pinfunction "B2_23") (pintype "input"))
    )
    (net (code "86") (name "LTDC_B3") (class "Default")
      (node (ref "IC4") (pin "154") (pinfunction "PG11_154") (pintype "bidirectional"))
      (node (ref "LCD1") (pin "24") (pinfunction "B3_24") (pintype "input"))
    )
    (net (code "87") (name "LTDC_B4") (class "Default")
      (node (ref "IC4") (pin "155") (pinfunction "PG12_155") (pintype "bidirectional"))
      (node (ref "LCD1") (pin "25") (pinfunction "B4_25") (pintype "input"))
    )
    (net (code "88") (name "LTDC_B5") (class "Default")
      (node (ref "IC4") (pin "174") (pinfunction "PI5_174") (pintype "bidirectional"))
      (node (ref "LCD1") (pin "26") (pinfunction "B5_26") (pintype "input"))
    )
    (net (code "89") (name "LTDC_B6") (class "Default")
      (node (ref "IC4") (pin "175") (pinfunction "PI6_175") (pintype "bidirectional"))
      (node (ref "LCD1") (pin "27") (pinfunction "B6_27") (pintype "input"))
    )
    (net (code "90") (name "LTDC_B7") (class "Default")
      (node (ref "IC4") (pin "176") (pinfunction "PI7_176") (pintype "bidirectional"))
      (node (ref "LCD1") (pin "28") (pinfunction "B7_28") (pintype "input"))
    )
    (net (code "91") (name "LTDC_CLK") (class "Default")
      (node (ref "IC4") (pin "115") (pinfunction "PG7_115") (pintype "bidirectional"))
      (node (ref "LCD1") (pin "30") (pinfunction "CLK_30") (pintype "input"))
    )
    (net (code "92") (name "LTDC_DE") (class "Default")
      (node (ref "IC4") (pin "28") (pinfunction "PF10_28") (pintype "bidirectional"))
      (node (ref "LCD1") (pin "34") (pinfunction "DE/NC2_34") (pintype "passive"))
    )
    (net (code "93") (name "LTDC_G2") (class "Default")
      (node (ref "IC4") (pin "52") (pinfunction "PA6_52") (pintype "bidirectional"))
      (node (ref "LCD1") (pin "15") (pinfunction "G2_15") (pintype "input"))
    )
    (net (code "94") (name "LTDC_G3") (class "Default")
      (node (ref "IC4") (pin "153") (pinfunction "PG10_153") (pintype "bidirectional"))
      (node (ref "LCD1") (pin "16") (pinfunction "G3_16") (pintype "input"))
    )
    (net (code "95") (name "LTDC_G4") (class "Default")
      (node (ref "IC4") (pin "45") (pinfunction "PH4_45") (pintype "bidirectional"))
      (node (ref "LCD1") (pin "17") (pinfunction "G4_17") (pintype "input"))
    )
    (net (code "96") (name "LTDC_G5") (class "Default")
      (node (ref "IC4") (pin "132") (pinfunction "PI0_132") (pintype "bidirectional"))
      (node (ref "LCD1") (pin "18") (pinfunction "G5_18") (pintype "input"))
    )
    (net (code "97") (name "LTDC_G6") (class "Default")
      (node (ref "IC4") (pin "13") (pinfunction "PI11_13") (pintype "bidirectional"))
      (node (ref "LCD1") (pin "19") (pinfunction "G6_19") (pintype "input"))
    )
    (net (code "98") (name "LTDC_G7") (class "Default")
      (node (ref "IC4") (pin "145") (pinfunction "PD3_145") (pintype "bidirectional"))
      (node (ref "LCD1") (pin "20") (pinfunction "G7_20") (pintype "input"))
    )
    (net (code "99") (name "LTDC_HSYNC") (class "Default")
      (node (ref "IC4") (pin "12") (pinfunction "PI10_12") (pintype "bidirectional"))
      (node (ref "LCD1") (pin "32") (pinfunction "HSYNC_32") (pintype "input"))
    )
    (net (code "100") (name "LTDC_R2") (class "Default")
      (node (ref "IC4") (pin "139") (pinfunction "PC10_139") (pintype "bidirectional"))
      (node (ref "LCD1") (pin "7") (pinfunction "R2_7") (pintype "input"))
    )
    (net (code "101") (name "LTDC_R3") (class "Default")
      (node (ref "IC4") (pin "56") (pinfunction "PB0_56") (pintype "bidirectional"))
      (node (ref "LCD1") (pin "8") (pinfunction "R3_8") (pintype "input"))
    )
    (net (code "102") (name "LTDC_R4") (class "Default")
      (node (ref "IC4") (pin "51") (pinfunction "PA5_51") (pintype "bidirectional"))
      (node (ref "LCD1") (pin "9") (pinfunction "R4_9") (pintype "input"))
    )
    (net (code "103") (name "LTDC_R5") (class "Default")
      (node (ref "IC4") (pin "32") (pinfunction "PC0_32") (pintype "bidirectional"))
      (node (ref "LCD1") (pin "10") (pinfunction "R5_10") (pintype "input"))
    )
    (net (code "104") (name "LTDC_R6") (class "Default")
      (node (ref "IC4") (pin "57") (pinfunction "PB1_57") (pintype "bidirectional"))
      (node (ref "LCD1") (pin "11") (pinfunction "R6_11") (pintype "input"))
    )
    (net (code "105") (name "LTDC_R7") (class "Default")
      (node (ref "IC4") (pin "114") (pinfunction "PG6_114") (pintype "bidirectional"))
      (node (ref "LCD1") (pin "12") (pinfunction "R7_12") (pintype "input"))
    )
    (net (code "106") (name "LTDC_VSYNC") (class "Default")
      (node (ref "IC4") (pin "11") (pinfunction "PI9_11") (pintype "bidirectional"))
      (node (ref "LCD1") (pin "33") (pinfunction "VSYNC_33") (pintype "input"))
    )
    (net (code "107") (name "MCLK_25") (class "Default")
      (node (ref "IC4") (pin "122") (pinfunction "PC9_122") (pintype "bidirectional"))
      (node (ref "RN1") (pin "1") (pinfunction "1_1") (pintype "passive"))
    )
    (net (code "108") (name "Net-(B1-+)") (class "Default")
      (node (ref "B1") (pin "2") (pinfunction "+_2") (pintype "passive"))
      (node (ref "JP2") (pin "NC") (pinfunction "NC_NC") (pintype "passive"))
    )
    (net (code "109") (name "Net-(C51-Pad1)") (class "Default")
      (node (ref "C51") (pin "1") (pinfunction "1_1") (pintype "passive"))
      (node (ref "R37") (pin "2") (pinfunction "2_2") (pintype "passive"))
    )
    (net (code "110") (name "Net-(C52-Pad1)") (class "Default")
      (node (ref "C52") (pin "1") (pinfunction "1_1") (pintype "passive"))
      (node (ref "R38") (pin "2") (pinfunction "2_2") (pintype "passive"))
    )
    (net (code "111") (name "Net-(C60-Pad1)") (class "Default")
      (node (ref "C60") (pin "1") (pinfunction "1_1") (pintype "passive"))
      (node (ref "R44") (pin "1") (pinfunction "1_1") (pintype "passive"))
      (node (ref "R45") (pin "2") (pinfunction "2_2") (pintype "passive"))
    )
    (net (code "112") (name "Net-(C62-Pad1)") (class "Default")
      (node (ref "C62") (pin "1") (pinfunction "1_1") (pintype "passive"))
      (node (ref "R48") (pin "1") (pinfunction "1_1") (pintype "passive"))
      (node (ref "R53") (pin "2") (pinfunction "2_2") (pintype "passive"))
    )
    (net (code "113") (name "Net-(F1-P$1)") (class "Default")
      (node (ref "F1") (pin "1") (pinfunction "P$1_1") (pintype "bidirectional"))
      (node (ref "X3") (pin "4") (pinfunction "1_4") (pintype "passive"))
    )
    (net (code "114") (name "Net-(F1-P$2)") (class "Default")
      (node (ref "F1") (pin "2") (pinfunction "P$2_2") (pintype "bidirectional"))
      (node (ref "IC1") (pin "4") (pinfunction "IO3_4") (pintype "bidirectional"))
      (node (ref "IC3") (pin "7") (pinfunction "OUT1_7") (pintype "output"))
      (node (ref "ZD1") (pin "C") (pinfunction "C_C") (pintype "passive"))
    )
    (net (code "115") (name "Net-(F2-P$1)") (class "Default")
      (node (ref "F2") (pin "1") (pinfunction "P$1_1") (pintype "bidirectional"))
      (node (ref "X3") (pin "5") (pinfunction "1_5") (pintype "passive"))
    )
    (net (code "116") (name "Net-(F2-P$2)") (class "Default")
      (node (ref "F2") (pin "2") (pinfunction "P$2_2") (pintype "bidirectional"))
      (node (ref "IC1") (pin "5") (pinfunction "IO4_5") (pintype "bidirectional"))
      (node (ref "IC3") (pin "5") (pinfunction "OUT2_5") (pintype "output"))
      (node (ref "ZD2") (pin "C") (pinfunction "C_C") (pintype "passive"))
    )
    (net (code "117") (name "Net-(IC1-IO1)") (class "Default")
      (node (ref "IC1") (pin "1") (pinfunction "IO1_1") (pintype "bidirectional"))
      (node (ref "IC2") (pin "1") (pinfunction "I_1") (pintype "input"))
      (node (ref "R3") (pin "2") (pinfunction "2_2") (pintype "passive"))
    )
    (net (code "118") (name "Net-(IC1-IO2)") (class "Default")
      (node (ref "IC1") (pin "2") (pinfunction "IO2_2") (pintype "bidirectional"))
      (node (ref "IC2") (pin "3") (pinfunction "I_3") (pintype "input"))
      (node (ref "R7") (pin "2") (pinfunction "2_2") (pintype "passive"))
    )
    (net (code "119") (name "Net-(IC2A-O)") (class "Default")
      (node (ref "IC2") (pin "6") (pinfunction "O_6") (pintype "output"))
      (node (ref "R4") (pin "1") (pinfunction "1_1") (pintype "passive"))
    )
    (net (code "120") (name "Net-(IC2B-O)") (class "Default")
      (node (ref "IC2") (pin "4") (pinfunction "O_4") (pintype "output"))
      (node (ref "R8") (pin "1") (pinfunction "1_1") (pintype "passive"))
    )
    (net (code "121") (name "Net-(IC4D-VCAPDSI)") (class "Default")
      (node (ref "IC4") (pin "100") (pinfunction "VCAPDSI_100") (pintype "power_in"))
      (node (ref "IC4") (pin "106") (pinfunction "VDD12DSI_106") (pintype "power_in"))
    )
    (net (code "122") (name "Net-(IC6-IO1)") (class "Default")
      (node (ref "IC6") (pin "1") (pinfunction "IO1_1") (pintype "bidirectional"))
      (node (ref "JP3") (pin "2") (pinfunction "2_2") (pintype "passive"))
      (node (ref "X4") (pin "3") (pinfunction "1_3") (pintype "passive"))
    )
    (net (code "123") (name "Net-(IC11-SW)") (class "Default")
      (node (ref "D2") (pin "A") (pinfunction "A_A") (pintype "passive"))
      (node (ref "IC11") (pin "1") (pinfunction "SW_1") (pintype "output"))
      (node (ref "L2") (pin "2") (pinfunction "2_2") (pintype "passive"))
    )
    (net (code "124") (name "Net-(IC11-VIN)") (class "Default")
      (node (ref "IC11") (pin "5") (pinfunction "VIN_5") (pintype "input"))
      (node (ref "R28") (pin "2") (pinfunction "2_2") (pintype "passive"))
    )
    (net (code "125") (name "Net-(IC13-BYPASS)") (class "Default")
      (node (ref "C56") (pin "2") (pinfunction "2_2") (pintype "passive"))
      (node (ref "IC13") (pin "2") (pinfunction "BYPASS_2") (pintype "input"))
    )
    (net (code "126") (name "Net-(IC13-IN+)") (class "Default")
      (node (ref "IC13") (pin "3") (pinfunction "IN+_3") (pintype "input"))
      (node (ref "R36") (pin "2") (pinfunction "2_2") (pintype "passive"))
      (node (ref "R37") (pin "1") (pinfunction "1_1") (pintype "passive"))
    )
    (net (code "127") (name "Net-(IC13-IN-)") (class "Default")
      (node (ref "IC13") (pin "4") (pinfunction "IN-_4") (pintype "input"))
      (node (ref "R38") (pin "1") (pinfunction "1_1") (pintype "passive"))
      (node (ref "R41") (pin "2") (pinfunction "2_2") (pintype "passive"))
    )
    (net (code "128") (name "Net-(IC13-VO+)") (class "Default")
      (node (ref "IC13") (pin "5") (pinfunction "VO+_5") (pintype "output"))
      (node (ref "R41") (pin "1") (pinfunction "1_1") (pintype "passive"))
      (node (ref "SP1") (pin "-") (pinfunction "-_-") (pintype "passive"))
    )
    (net (code "129") (name "Net-(IC13-VO-)") (class "Default")
      (node (ref "IC13") (pin "8") (pinfunction "VO-_8") (pintype "output"))
      (node (ref "R36") (pin "1") (pinfunction "1_1") (pintype "passive"))
      (node (ref "SP1") (pin "+") (pinfunction "+_+") (pintype "passive"))
    )
    (net (code "130") (name "Net-(IC14-IO1)") (class "Default")
      (node (ref "IC14") (pin "1") (pinfunction "IO1_1") (pintype "bidirectional"))
      (node (ref "IC15") (pin "18") (pinfunction "X+_18") (pintype "bidirectional"))
      (node (ref "LCD1") (pin "37") (pinfunction "XR_37") (pintype "passive"))
    )
    (net (code "131") (name "Net-(IC14-IO2)") (class "Default")
      (node (ref "C58") (pin "1") (pinfunction "1_1") (pintype "passive"))
      (node (ref "IC14") (pin "2") (pinfunction "IO2_2") (pintype "bidirectional"))
      (node (ref "IC15") (pin "16") (pinfunction "Y-_16") (pintype "bidirectional"))
      (node (ref "LCD1") (pin "38") (pinfunction "YD_38") (pintype "passive"))
    )
    (net (code "132") (name "Net-(IC14-IO3)") (class "Default")
      (node (ref "C57") (pin "1") (pinfunction "1_1") (pintype "passive"))
      (node (ref "IC14") (pin "4") (pinfunction "IO3_4") (pintype "bidirectional"))
      (node (ref "IC15") (pin "19") (pinfunction "X-_19") (pintype "bidirectional"))
      (node (ref "LCD1") (pin "39") (pinfunction "XL_39") (pintype "passive"))
      (node (ref "R39") (pin "2") (pinfunction "2_2") (pintype "passive"))
    )
    (net (code "133") (name "Net-(IC14-IO4)") (class "Default")
      (node (ref "IC14") (pin "5") (pinfunction "IO4_5") (pintype "bidirectional"))
      (node (ref "IC15") (pin "15") (pinfunction "Y+_15") (pintype "bidirectional"))
      (node (ref "LCD1") (pin "40") (pinfunction "YU_40") (pintype "passive"))
    )
    (net (code "134") (name "Net-(IC15-SIQ)") (class "Default")
      (node (ref "IC15") (pin "6") (pinfunction "SIQ_6") (pintype "bidirectional"))
      (node (ref "R42") (pin "2") (pinfunction "2_2") (pintype "passive"))
    )
    (net (code "135") (name "Net-(IC15-WAKE)") (class "Default")
      (node (ref "IC15") (pin "5") (pinfunction "WAKE_5") (pintype "input"))
      (node (ref "R39") (pin "1") (pinfunction "1_1") (pintype "passive"))
    )
    (net (code "136") (name "Net-(IC16-IO1)") (class "Default")
      (node (ref "IC16") (pin "1") (pinfunction "IO1_1") (pintype "bidirectional"))
      (node (ref "IC17") (pin "17") (pinfunction "TD+_17") (pintype "bidirectional"))
      (node (ref "R44") (pin "2") (pinfunction "2_2") (pintype "passive"))
      (node (ref "X6") (pin "1") (pinfunction "TD+_1") (pintype "input"))
    )
    (net (code "137") (name "Net-(IC16-IO2)") (class "Default")
      (node (ref "IC16") (pin "2") (pinfunction "IO2_2") (pintype "bidirectional"))
      (node (ref "IC17") (pin "16") (pinfunction "TD-_16") (pintype "bidirectional"))
      (node (ref "R45") (pin "1") (pinfunction "1_1") (pintype "passive"))
      (node (ref "X6") (pin "2") (pinfunction "TD-_2") (pintype "input"))
    )
    (net (code "138") (name "Net-(IC16-IO3)") (class "Default")
      (node (ref "IC16") (pin "4") (pinfunction "IO3_4") (pintype "bidirectional"))
      (node (ref "IC17") (pin "14") (pinfunction "RD+_14") (pintype "bidirectional"))
      (node (ref "R48") (pin "2") (pinfunction "2_2") (pintype "passive"))
      (node (ref "X6") (pin "7") (pinfunction "RD+_7") (pintype "input"))
    )
    (net (code "139") (name "Net-(IC16-IO4)") (class "Default")
      (node (ref "IC16") (pin "5") (pinfunction "IO4_5") (pintype "bidirectional"))
      (node (ref "IC17") (pin "13") (pinfunction "RD-_13") (pintype "bidirectional"))
      (node (ref "R53") (pin "1") (pinfunction "1_1") (pintype "passive"))
      (node (ref "X6") (pin "8") (pinfunction "RD-_8") (pintype "input"))
    )
    (net (code "140") (name "Net-(IC17-CRS{slash}CRS_DV{slash}LED_CFG)") (class "Default")
      (node (ref "IC17") (pin "40") (pinfunction "CRS/CRS_DV/LED_CFG_40") (pintype "output"))
      (node (ref "RN1") (pin "5") (pinfunction "2_5") (pintype "passive"))
    )
    (net (code "141") (name "Net-(IC17-MDIX_EN(RX_ER))") (class "Default")
      (node (ref "IC17") (pin "41") (pinfunction "MDIX_EN(RX_ER)_41") (pintype "output"))
      (node (ref "RN2") (pin "8") (pinfunction "2_8") (pintype "passive"))
    )
    (net (code "142") (name "Net-(IC17-MII_MODE(RX_DV))") (class "Default")
      (node (ref "IC17") (pin "39") (pinfunction "MII_MODE(RX_DV)_39") (pintype "output"))
      (node (ref "JP7") (pin "2") (pinfunction "2_2") (pintype "passive"))
      (node (ref "RN1") (pin "6") (pinfunction "2_6") (pintype "passive"))
    )
    (net (code "143") (name "Net-(IC17-PFBIN1)") (class "Default")
      (node (ref "C64") (pin "1") (pinfunction "1_1") (pintype "passive"))
      (node (ref "C65") (pin "1") (pinfunction "1_1") (pintype "passive"))
      (node (ref "C66") (pin "+") (pinfunction "+_+") (pintype "passive"))
      (node (ref "C67") (pin "1") (pinfunction "1_1") (pintype "passive"))
      (node (ref "IC17") (pin "18") (pinfunction "PFBIN1_18") (pintype "input"))
      (node (ref "IC17") (pin "23") (pinfunction "PFBOUT_23") (pintype "output"))
      (node (ref "IC17") (pin "37") (pinfunction "PFBIN2_37") (pintype "input"))
    )
    (net (code "144") (name "Net-(IC17-PHYAD0(COL))") (class "Default")
      (node (ref "IC17") (pin "42") (pinfunction "PHYAD0(COL)_42") (pintype "output"))
      (node (ref "RN2") (pin "7") (pinfunction "2_7") (pintype "passive"))
    )
    (net (code "145") (name "Net-(IC17-PHYAD1(RXD1_0))") (class "Default")
      (node (ref "IC17") (pin "43") (pinfunction "PHYAD1(RXD1_0)_43") (pintype "output"))
      (node (ref "RN2") (pin "6") (pinfunction "2_6") (pintype "passive"))
    )
    (net (code "146") (name "Net-(IC17-PHYAD2(RXD1_1))") (class "Default")
      (node (ref "IC17") (pin "44") (pinfunction "PHYAD2(RXD1_1)_44") (pintype "output"))
      (node (ref "RN2") (pin "5") (pinfunction "2_5") (pintype "passive"))
    )
    (net (code "147") (name "Net-(IC17-PHYAD3(RXD1_2))") (class "Default")
      (node (ref "IC17") (pin "45") (pinfunction "PHYAD3(RXD1_2)_45") (pintype "output"))
      (node (ref "RN3") (pin "8") (pinfunction "2_8") (pintype "passive"))
    )
    (net (code "148") (name "Net-(IC17-PHYAD4(RXD1_3))") (class "Default")
      (node (ref "IC17") (pin "46") (pinfunction "PHYAD4(RXD1_3)_46") (pintype "output"))
      (node (ref "RN3") (pin "7") (pinfunction "2_7") (pintype "passive"))
    )
    (net (code "149") (name "Net-(IC17-PWR_DOWN{slash}INT)") (class "Default")
      (node (ref "IC17") (pin "7") (pinfunction "PWR_DOWN/INT_7") (pintype "input"))
      (node (ref "JP9") (pin "2") (pinfunction "2_2") (pintype "passive"))
    )
    (net (code "150") (name "Net-(IC17-RBIAS)") (class "Default")
      (node (ref "IC17") (pin "24") (pinfunction "RBIAS_24") (pintype "input"))
      (node (ref "R59") (pin "2") (pinfunction "2_2") (pintype "passive"))
    )
    (net (code "151") (name "Net-(IC17-RESERVED-20)") (class "Default")
      (node (ref "IC17") (pin "20") (pinfunction "RESERVED-20_20") (pintype "bidirectional"))
      (node (ref "R58") (pin "2") (pinfunction "2_2") (pintype "passive"))
    )
    (net (code "152") (name "Net-(IC17-RESERVED-21)") (class "Default")
      (node (ref "IC17") (pin "21") (pinfunction "RESERVED-21_21") (pintype "bidirectional"))
      (node (ref "R57") (pin "2") (pinfunction "2_2") (pintype "passive"))
    )
    (net (code "153") (name "Net-(IC17-RX_CLK)") (class "Default")
      (node (ref "IC17") (pin "38") (pinfunction "RX_CLK_38") (pintype "output"))
      (node (ref "RN1") (pin "7") (pinfunction "2_7") (pintype "passive"))
    )
    (net (code "154") (name "Net-(IC17-TXD_0)") (class "Default")
      (node (ref "IC17") (pin "3") (pinfunction "TXD_0_3") (pintype "input"))
      (node (ref "RN4") (pin "8") (pinfunction "2_8") (pintype "passive"))
    )
    (net (code "155") (name "Net-(IC17-TXD_1)") (class "Default")
      (node (ref "IC17") (pin "4") (pinfunction "TXD_1_4") (pintype "input"))
      (node (ref "RN4") (pin "7") (pinfunction "2_7") (pintype "passive"))
    )
    (net (code "156") (name "Net-(IC17-TXD_2)") (class "Default")
      (node (ref "IC17") (pin "5") (pinfunction "TXD_2_5") (pintype "input"))
      (node (ref "RN4") (pin "6") (pinfunction "2_6") (pintype "passive"))
    )
    (net (code "157") (name "Net-(IC17-TXD_3{slash}SNI_MODE)") (class "Default")
      (node (ref "IC17") (pin "6") (pinfunction "TXD_3/SNI_MODE_6") (pintype "input"))
      (node (ref "RN4") (pin "5") (pinfunction "2_5") (pintype "passive"))
    )
    (net (code "158") (name "Net-(IC17-TX_CLK)") (class "Default")
      (node (ref "IC17") (pin "1") (pinfunction "TX_CLK_1") (pintype "output"))
      (node (ref "RN3") (pin "6") (pinfunction "2_6") (pintype "passive"))
    )
    (net (code "159") (name "Net-(IC17-TX_EN)") (class "Default")
      (node (ref "IC17") (pin "2") (pinfunction "TX_EN_2") (pintype "input"))
      (node (ref "RN3") (pin "5") (pinfunction "2_5") (pintype "passive"))
    )
    (net (code "160") (name "Net-(IC17-X1)") (class "Default")
      (node (ref "IC17") (pin "34") (pinfunction "X1_34") (pintype "input"))
      (node (ref "RN1") (pin "8") (pinfunction "2_8") (pintype "passive"))
    )
    (net (code "161") (name "Net-(JP5-Pad2)") (class "Default")
      (node (ref "JP5") (pin "2") (pinfunction "2_2") (pintype "passive"))
      (node (ref "R49") (pin "2") (pinfunction "2_2") (pintype "passive"))
    )
    (net (code "162") (name "Net-(JP6-Pad1)") (class "Default")
      (node (ref "JP6") (pin "1") (pinfunction "1_1") (pintype "passive"))
      (node (ref "JP8") (pin "1") (pinfunction "1_1") (pintype "passive"))
      (node (ref "RN2") (pin "1") (pinfunction "1_1") (pintype "passive"))
    )
    (net (code "163") (name "Net-(JP6-Pad2)") (class "Default")
      (node (ref "JP6") (pin "2") (pinfunction "2_2") (pintype "passive"))
      (node (ref "R46") (pin "2") (pinfunction "2_2") (pintype "passive"))
    )
    (net (code "164") (name "Net-(JP7-Pad1)") (class "Default")
      (node (ref "JP7") (pin "1") (pinfunction "1_1") (pintype "passive"))
      (node (ref "R51") (pin "2") (pinfunction "2_2") (pintype "passive"))
    )
    (net (code "165") (name "Net-(JP9-Pad1)") (class "Default")
      (node (ref "JP9") (pin "1") (pinfunction "1_1") (pintype "passive"))
      (node (ref "R60") (pin "2") (pinfunction "2_2") (pintype "passive"))
    )
    (net (code "166") (name "Net-(LCD1-RESET)") (class "Default")
      (node (ref "JP4") (pin "COM") (pinfunction "COM_COM") (pintype "passive"))
      (node (ref "LCD1") (pin "36") (pinfunction "RESET_36") (pintype "input"))
    )
    (net (code "167") (name "Net-(Q1-PadB)") (class "Default")
      (node (ref "Q1") (pin "B") (pinfunction "B_B") (pintype "passive"))
      (node (ref "R32") (pin "2") (pinfunction "2_2") (pintype "passive"))
    )
    (net (code "168") (name "Net-(Q1-PadC)") (class "Default")
      (node (ref "Q1") (pin "C") (pinfunction "C_C") (pintype "passive"))
      (node (ref "R29") (pin "1") (pinfunction "1_1") (pintype "passive"))
    )
    (net (code "169") (name "Net-(R1-Pad2)") (class "Default")
      (node (ref "R1") (pin "2") (pinfunction "2_2") (pintype "passive"))
      (node (ref "R5") (pin "2") (pinfunction "2_2") (pintype "passive"))
      (node (ref "SW1") (pin "B") (pinfunction "B_B") (pintype "passive"))
    )
    (net (code "170") (name "Net-(R2-Pad1)") (class "Default")
      (node (ref "R2") (pin "1") (pinfunction "1_1") (pintype "passive"))
      (node (ref "X3") (pin "1") (pinfunction "1_1") (pintype "passive"))
    )
    (net (code "171") (name "Net-(R2-Pad2)") (class "Default")
      (node (ref "R2") (pin "2") (pinfunction "2_2") (pintype "passive"))
      (node (ref "R3") (pin "1") (pinfunction "1_1") (pintype "passive"))
    )
    (net (code "172") (name "Net-(R6-Pad2)") (class "Default")
      (node (ref "R6") (pin "2") (pinfunction "2_2") (pintype "passive"))
      (node (ref "R7") (pin "1") (pinfunction "1_1") (pintype "passive"))
    )
    (net (code "173") (name "Net-(R10-Pad2)") (class "Default")
      (node (ref "R10") (pin "2") (pinfunction "2_2") (pintype "passive"))
      (node (ref "R9") (pin "2") (pinfunction "2_2") (pintype "passive"))
      (node (ref "SW1") (pin "A") (pinfunction "A_A") (pintype "passive"))
    )
    (net (code "174") (name "Net-(R29-Pad2)") (class "Default")
      (node (ref "R29") (pin "2") (pinfunction "2_2") (pintype "passive"))
      (node (ref "VBUS") (pin "C") (pinfunction "C_C") (pintype "passive"))
    )
    (net (code "175") (name "Net-(R42-Pad1)") (class "Default")
      (node (ref "R42") (pin "1") (pinfunction "1_1") (pintype "passive"))
      (node (ref "TOUCH") (pin "A") (pinfunction "A_A") (pintype "passive"))
    )
    (net (code "176") (name "Net-(R50-Pad2)") (class "Default")
      (node (ref "R50") (pin "2") (pinfunction "2_2") (pintype "passive"))
      (node (ref "SPEED") (pin "A") (pinfunction "A_A") (pintype "passive"))
    )
    (net (code "177") (name "Net-(X3B-1)") (class "Default")
      (node (ref "R6") (pin "1") (pinfunction "1_1") (pintype "passive"))
      (node (ref "X3") (pin "2") (pinfunction "1_2") (pintype "passive"))
    )
    (net (code "178") (name "Net-(X6-GREEN-C)") (class "Default")
      (node (ref "R56") (pin "1") (pinfunction "1_1") (pintype "passive"))
      (node (ref "X6") (pin "10") (pinfunction "GREEN-C_10") (pintype "passive"))
    )
    (net (code "179") (name "Net-(X6-YELLOW-C)") (class "Default")
      (node (ref "R55") (pin "1") (pinfunction "1_1") (pintype "passive"))
      (node (ref "X6") (pin "11") (pinfunction "YELLOW-C_11") (pintype "passive"))
    )
    (net (code "180") (name "OE_SYNC") (class "Default")
      (node (ref "IC4") (pin "94") (pinfunction "PD13_94") (pintype "bidirectional"))
      (node (ref "X1") (pin "39") (pinfunction "1_39") (pintype "passive"))
    )
    (net (code "181") (name "OUT_PAR") (class "Default")
      (node (ref "IC4") (pin "140") (pinfunction "PC11_140") (pintype "bidirectional"))
      (node (ref "X1") (pin "38") (pinfunction "1_38") (pintype "passive"))
    )
    (net (code "182") (name "OUT_SER") (class "Default")
      (node (ref "IC4") (pin "152") (pinfunction "PG9_152") (pintype "bidirectional"))
      (node (ref "X1") (pin "37") (pinfunction "1_37") (pintype "passive"))
    )
    (net (code "183") (name "PE") (class "Default")
      (node (ref "X2") (pin "1") (pinfunction "1_1") (pintype "passive"))
      (node (ref "X2") (pin "2") (pinfunction "1_2") (pintype "passive"))
      (node (ref "X5") (pin "M1") (pinfunction "SHIELD_M1") (pintype "passive"))
      (node (ref "X5") (pin "M2") (pinfunction "SHIELD_M2") (pintype "passive"))
      (node (ref "X6") (pin "SH") (pinfunction "SH_SH") (pintype "passive"))
      (node (ref "X6") (pin "SH2") (pinfunction "SH_SH2") (pintype "passive"))
    )
    (net (code "184") (name "PWR_DIRECT") (class "Default")
      (node (ref "IC4") (pin "110") (pinfunction "PG2_110") (pintype "bidirectional"))
      (node (ref "X2") (pin "12") (pinfunction "1_12") (pintype "passive"))
    )
    (net (code "185") (name "PWR_SSTART") (class "Default")
      (node (ref "IC4") (pin "111") (pinfunction "PG3_111") (pintype "bidirectional"))
      (node (ref "X2") (pin "11") (pinfunction "1_11") (pintype "passive"))
    )
    (net (code "186") (name "RCC_OSC_IN") (class "Default")
      (node (ref "C8") (pin "2") (pinfunction "2_2") (pintype "passive"))
      (node (ref "IC4") (pin "29") (pinfunction "PH0_29") (pintype "bidirectional"))
      (node (ref "R14") (pin "2") (pinfunction "2_2") (pintype "passive"))
      (node (ref "Y1") (pin "2") (pinfunction "2_2") (pintype "passive"))
    )
    (net (code "187") (name "RCC_OSC_OUT") (class "Default")
      (node (ref "C9") (pin "2") (pinfunction "2_2") (pintype "passive"))
      (node (ref "IC4") (pin "30") (pinfunction "PH1_30") (pintype "bidirectional"))
      (node (ref "R14") (pin "1") (pinfunction "1_1") (pintype "passive"))
      (node (ref "Y1") (pin "1") (pinfunction "1_1") (pintype "passive"))
    )
    (net (code "188") (name "RTCK") (class "Default")
      (node (ref "R22") (pin "1") (pinfunction "1_1") (pintype "passive"))
      (node (ref "X4") (pin "11") (pinfunction "1_11") (pintype "passive"))
    )
    (net (code "189") (name "SDMMC1_CK") (class "Default")
      (node (ref "IC4") (pin "141") (pinfunction "PC12_141") (pintype "bidirectional"))
      (node (ref "J1") (pin "5") (pinfunction "CLK_5") (pintype "passive"))
    )
    (net (code "190") (name "SDMMC1_CMD") (class "Default")
      (node (ref "IC4") (pin "144") (pinfunction "PD2_144") (pintype "bidirectional"))
      (node (ref "J1") (pin "3") (pinfunction "CMD_3") (pintype "passive"))
      (node (ref "R27") (pin "2") (pinfunction "2_2") (pintype "passive"))
    )
    (net (code "191") (name "SDMMC1_D0") (class "Default")
      (node (ref "IC4") (pin "121") (pinfunction "PC8_121") (pintype "bidirectional"))
      (node (ref "J1") (pin "7") (pinfunction "DAT0_7") (pintype "passive"))
      (node (ref "R26") (pin "2") (pinfunction "2_2") (pintype "passive"))
    )
    (net (code "192") (name "SD_DETECT") (class "Default")
      (node (ref "IC4") (pin "24") (pinfunction "PF6_24") (pintype "bidirectional"))
      (node (ref "J1") (pin "SW1") (pinfunction "SW1_SW1") (pintype "passive"))
    )
    (net (code "193") (name "SPI2_CLK") (class "Default")
      (node (ref "IC4") (pin "133") (pinfunction "PI1_133") (pintype "bidirectional"))
      (node (ref "X1") (pin "9") (pinfunction "1_9") (pintype "passive"))
    )
    (net (code "194") (name "SPI2_CSA") (class "Default")
      (node (ref "IC4") (pin "93") (pinfunction "PD12_93") (pintype "bidirectional"))
      (node (ref "X1") (pin "15") (pinfunction "1_15") (pintype "passive"))
    )
    (net (code "195") (name "SPI2_CSB") (class "Default")
      (node (ref "IC4") (pin "92") (pinfunction "PD11_92") (pintype "bidirectional"))
      (node (ref "X1") (pin "17") (pinfunction "1_17") (pintype "passive"))
    )
    (net (code "196") (name "SPI2_IRQ") (class "Default")
      (node (ref "IC4") (pin "123") (pinfunction "PA8_123") (pintype "bidirectional"))
      (node (ref "X1") (pin "19") (pinfunction "1_19") (pintype "passive"))
    )
    (net (code "197") (name "SPI2_MISO") (class "Default")
      (node (ref "IC4") (pin "87") (pinfunction "PB14_87") (pintype "bidirectional"))
      (node (ref "X1") (pin "11") (pinfunction "1_11") (pintype "passive"))
    )
    (net (code "198") (name "SPI2_MOSI") (class "Default")
      (node (ref "IC4") (pin "134") (pinfunction "PI3_134") (pintype "bidirectional"))
      (node (ref "X1") (pin "13") (pinfunction "1_13") (pintype "passive"))
    )
    (net (code "199") (name "SPI4_CLK") (class "Default")
      (node (ref "IC4") (pin "1") (pinfunction "PE2_1") (pintype "bidirectional"))
      (node (ref "X1") (pin "10") (pinfunction "1_10") (pintype "passive"))
    )
    (net (code "200") (name "SPI4_CSA") (class "Default")
      (node (ref "IC4") (pin "2") (pinfunction "PE3_2") (pintype "bidirectional"))
      (node (ref "X1") (pin "16") (pinfunction "1_16") (pintype "passive"))
    )
    (net (code "201") (name "SPI4_CSB") (class "Default")
      (node (ref "IC4") (pin "3") (pinfunction "PE4_3") (pintype "bidirectional"))
      (node (ref "X1") (pin "18") (pinfunction "1_18") (pintype "passive"))
    )
    (net (code "202") (name "SPI4_IRQ") (class "Default")
      (node (ref "IC4") (pin "168") (pinfunction "PB9_168") (pintype "bidirectional"))
      (node (ref "X1") (pin "20") (pinfunction "1_20") (pintype "passive"))
    )
    (net (code "203") (name "SPI4_MISO") (class "Default")
      (node (ref "IC4") (pin "4") (pinfunction "PE5_4") (pintype "bidirectional"))
      (node (ref "X1") (pin "12") (pinfunction "1_12") (pintype "passive"))
    )
    (net (code "204") (name "SPI4_MOSI") (class "Default")
      (node (ref "IC4") (pin "5") (pinfunction "PE6_5") (pintype "bidirectional"))
      (node (ref "X1") (pin "14") (pinfunction "1_14") (pintype "passive"))
    )
    (net (code "205") (name "SPI5_CLK") (class "Default")
      (node (ref "IC4") (pin "25") (pinfunction "PF7_25") (pintype "bidirectional"))
      (node (ref "X1") (pin "23") (pinfunction "1_23") (pintype "passive"))
    )
    (net (code "206") (name "SPI5_CSA") (class "Default")
      (node (ref "IC4") (pin "157") (pinfunction "PG14_157") (pintype "bidirectional"))
      (node (ref "X1") (pin "29") (pinfunction "1_29") (pintype "passive"))
    )
    (net (code "207") (name "SPI5_CSB") (class "Default")
      (node (ref "IC4") (pin "156") (pinfunction "PG13_156") (pintype "bidirectional"))
      (node (ref "X1") (pin "31") (pinfunction "1_31") (pintype "passive"))
    )
    (net (code "208") (name "SPI5_IRQ") (class "Default")
      (node (ref "IC4") (pin "79") (pinfunction "PB10_79") (pintype "bidirectional"))
      (node (ref "JP8") (pin "2") (pinfunction "2_2") (pintype "passive"))
      (node (ref "X1") (pin "33") (pinfunction "1_33") (pintype "passive"))
    )
    (net (code "209") (name "SPI5_MISO") (class "Default")
      (node (ref "IC4") (pin "26") (pinfunction "PF8_26") (pintype "bidirectional"))
      (node (ref "X1") (pin "25") (pinfunction "1_25") (pintype "passive"))
    )
    (net (code "210") (name "SPI5_MOSI") (class "Default")
      (node (ref "IC4") (pin "27") (pinfunction "PF9_27") (pintype "bidirectional"))
      (node (ref "X1") (pin "27") (pinfunction "1_27") (pintype "passive"))
    )
    (net (code "211") (name "SYS_JTCK-SWCLK") (class "Default")
      (node (ref "IC4") (pin "137") (pinfunction "PA14_137") (pintype "bidirectional"))
      (node (ref "R21") (pin "1") (pinfunction "1_1") (pintype "passive"))
    )
    (net (code "212") (name "SYS_JTDI") (class "Default")
      (node (ref "IC4") (pin "138") (pinfunction "PA15_138") (pintype "bidirectional"))
      (node (ref "IC6") (pin "5") (pinfunction "IO4_5") (pintype "bidirectional"))
      (node (ref "X4") (pin "5") (pinfunction "1_5") (pintype "passive"))
    )
    (net (code "213") (name "SYS_JTDO-SWO") (class "Default")
      (node (ref "IC4") (pin "161") (pinfunction "PB3_161") (pintype "bidirectional"))
      (node (ref "IC7") (pin "5") (pinfunction "IO4_5") (pintype "bidirectional"))
      (node (ref "X4") (pin "13") (pinfunction "1_13") (pintype "passive"))
    )
    (net (code "214") (name "SYS_JTMS-SWDIO") (class "Default")
      (node (ref "IC4") (pin "128") (pinfunction "PA13_128") (pintype "bidirectional"))
      (node (ref "R20") (pin "1") (pinfunction "1_1") (pintype "passive"))
    )
    (net (code "215") (name "SYS_JTRST") (class "Default")
      (node (ref "IC4") (pin "162") (pinfunction "PB4_162") (pintype "bidirectional"))
      (node (ref "JP3") (pin "1") (pinfunction "1_1") (pintype "passive"))
      (node (ref "R19") (pin "2") (pinfunction "2_2") (pintype "passive"))
    )
    (net (code "216") (name "TCK") (class "Default")
      (node (ref "IC7") (pin "1") (pinfunction "IO1_1") (pintype "bidirectional"))
      (node (ref "R21") (pin "2") (pinfunction "2_2") (pintype "passive"))
      (node (ref "X4") (pin "9") (pinfunction "1_9") (pintype "passive"))
    )
    (net (code "217") (name "TFT_BRIGHTNESS") (class "Default")
      (node (ref "IC11") (pin "4") (pinfunction "CTRL_4") (pintype "input"))
      (node (ref "IC4") (pin "88") (pinfunction "PB15_88") (pintype "bidirectional"))
    )
    (net (code "218") (name "TMS") (class "Default")
      (node (ref "IC6") (pin "4") (pinfunction "IO3_4") (pintype "bidirectional"))
      (node (ref "R20") (pin "2") (pinfunction "2_2") (pintype "passive"))
      (node (ref "X4") (pin "7") (pinfunction "1_7") (pintype "passive"))
    )
    (net (code "219") (name "USB_D_N") (class "Default")
      (node (ref "IC12") (pin "1") (pinfunction "IO1_1") (pintype "bidirectional"))
      (node (ref "R33") (pin "1") (pinfunction "1_1") (pintype "passive"))
      (node (ref "X5") (pin "2") (pinfunction "2_2") (pintype "passive"))
    )
    (net (code "220") (name "USB_D_P") (class "Default")
      (node (ref "IC12") (pin "4") (pinfunction "IO3_4") (pintype "bidirectional"))
      (node (ref "R34") (pin "1") (pinfunction "1_1") (pintype "passive"))
      (node (ref "X5") (pin "3") (pinfunction "3_3") (pintype "passive"))
    )
    (net (code "221") (name "USB_OTG_FS_D_N") (class "Default")
      (node (ref "IC4") (pin "126") (pinfunction "PA11_126") (pintype "bidirectional"))
      (node (ref "R33") (pin "2") (pinfunction "2_2") (pintype "passive"))
    )
    (net (code "222") (name "USB_OTG_FS_D_P") (class "Default")
      (node (ref "IC4") (pin "127") (pinfunction "PA12_127") (pintype "bidirectional"))
      (node (ref "R34") (pin "2") (pinfunction "2_2") (pintype "passive"))
    )
    (net (code "223") (name "USB_OTG_FS_ID") (class "Default")
      (node (ref "IC4") (pin "125") (pinfunction "PA10_125") (pintype "bidirectional"))
      (node (ref "X5") (pin "4") (pinfunction "4_4") (pintype "passive"))
    )
    (net (code "224") (name "USB_OTG_FS_PSO") (class "Default")
      (node (ref "IC10") (pin "4") (pinfunction "EN_4") (pintype "input"))
      (node (ref "IC4") (pin "147") (pinfunction "PD5_147") (pintype "bidirectional"))
    )
    (net (code "225") (name "USB_OTG_FS_VBUS") (class "Default")
      (node (ref "C47") (pin "+") (pinfunction "+_+") (pintype "passive"))
      (node (ref "C49") (pin "2") (pinfunction "2_2") (pintype "passive"))
      (node (ref "IC10") (pin "1") (pinfunction "OUT_1") (pintype "output"))
      (node (ref "IC12") (pin "6") (pinfunction "VCC_6") (pintype "passive"))
      (node (ref "IC4") (pin "124") (pinfunction "PA9_124") (pintype "bidirectional"))
      (node (ref "R32") (pin "1") (pinfunction "1_1") (pintype "passive"))
      (node (ref "X5") (pin "1") (pinfunction "1_1") (pintype "passive"))
    )
    (net (code "226") (name "USER_SW") (class "Default")
      (node (ref "C3") (pin "2") (pinfunction "2_2") (pintype "passive"))
      (node (ref "IC4") (pin "163") (pinfunction "PB5_163") (pintype "bidirectional"))
      (node (ref "SW2") (pin "1") (pinfunction "1_1") (pintype "passive"))
    )
    (net (code "227") (name "VBAT") (class "Default")
      (node (ref "IC4") (pin "6") (pinfunction "VBAT_6") (pintype "power_in"))
      (node (ref "JP2") (pin "COM") (pinfunction "COM_COM") (pintype "passive"))
    )
    (net (code "228") (name "VCAP1") (class "Default")
      (node (ref "C34") (pin "1") (pinfunction "1_1") (pintype "passive"))
      (node (ref "IC4") (pin "81") (pinfunction "VCAP_1_81") (pintype "power_in"))
    )
    (net (code "229") (name "VCAP2") (class "Default")
      (node (ref "C33") (pin "1") (pinfunction "1_1") (pintype "passive"))
      (node (ref "IC4") (pin "129") (pinfunction "VCAP_2_129") (pintype "power_in"))
    )
    (net (code "230") (name "VDD") (class "Default")
      (node (ref "C13") (pin "1") (pinfunction "1_1") (pintype "passive"))
      (node (ref "C14") (pin "1") (pinfunction "1_1") (pintype "passive"))
      (node (ref "C15") (pin "1") (pinfunction "1_1") (pintype "passive"))
      (node (ref "C16") (pin "1") (pinfunction "1_1") (pintype "passive"))
      (node (ref "C17") (pin "1") (pinfunction "1_1") (pintype "passive"))
      (node (ref "C18") (pin "1") (pinfunction "1_1") (pintype "passive"))
      (node (ref "C19") (pin "+") (pinfunction "+_+") (pintype "passive"))
      (node (ref "C20") (pin "1") (pinfunction "1_1") (pintype "passive"))
      (node (ref "C21") (pin "1") (pinfunction "1_1") (pintype "passive"))
      (node (ref "C22") (pin "1") (pinfunction "1_1") (pintype "passive"))
      (node (ref "C23") (pin "1") (pinfunction "1_1") (pintype "passive"))
      (node (ref "C24") (pin "1") (pinfunction "1_1") (pintype "passive"))
      (node (ref "C25") (pin "1") (pinfunction "1_1") (pintype "passive"))
      (node (ref "C26") (pin "1") (pinfunction "1_1") (pintype "passive"))
      (node (ref "C27") (pin "1") (pinfunction "1_1") (pintype "passive"))
      (node (ref "C28") (pin "1") (pinfunction "1_1") (pintype "passive"))
      (node (ref "C29") (pin "1") (pinfunction "1_1") (pintype "passive"))
      (node (ref "C30") (pin "1") (pinfunction "1_1") (pintype "passive"))
      (node (ref "IC4") (pin "118") (pinfunction "VDDUSB_118") (pintype "power_in"))
      (node (ref "IC4") (pin "131") (pinfunction "VDD_10_131") (pintype "power_in"))
      (node (ref "IC4") (pin "136") (pinfunction "VDD_11_136") (pintype "power_in"))
      (node (ref "IC4") (pin "149") (pinfunction "VDDSDMMC_149") (pintype "power_in"))
      (node (ref "IC4") (pin "15") (pinfunction "VDD_2_15") (pintype "power_in"))
      (node (ref "IC4") (pin "159") (pinfunction "VDD_12_159") (pintype "power_in"))
      (node (ref "IC4") (pin "171") (pinfunction "PDR_ON_171") (pintype "passive"))
      (node (ref "IC4") (pin "172") (pinfunction "VDD_172") (pintype "power_in"))
      (node (ref "IC4") (pin "23") (pinfunction "VDD_3_23") (pintype "power_in"))
      (node (ref "IC4") (pin "36") (pinfunction "VDD_4_36") (pintype "power_in"))
      (node (ref "IC4") (pin "49") (pinfunction "VDD_5_49") (pintype "power_in"))
      (node (ref "IC4") (pin "62") (pinfunction "VDD_6_62") (pintype "power_in"))
      (node (ref "IC4") (pin "72") (pinfunction "VDD_7_72") (pintype "power_in"))
      (node (ref "IC4") (pin "82") (pinfunction "VDD_8_82") (pintype "power_in"))
      (node (ref "IC4") (pin "96") (pinfunction "VDD_9_96") (pintype "power_in"))
      (node (ref "IC4") (pin "99") (pinfunction "VDDDSI_99") (pintype "power_in"))
      (node (ref "JP1") (pin "NO") (pinfunction "NO_NO") (pintype "passive"))
      (node (ref "JP2") (pin "NO") (pinfunction "NO_NO") (pintype "passive"))
      (node (ref "L1") (pin "P$1") (pinfunction "1_P$1") (pintype "passive"))
      (node (ref "R11") (pin "1") (pinfunction "1_1") (pintype "passive"))
      (node (ref "R17") (pin "2") (pinfunction "2_2") (pintype "passive"))
    )
    (net (code "231") (name "VDDA") (class "Default")
      (node (ref "C31") (pin "1") (pinfunction "1_1") (pintype "passive"))
      (node (ref "C32") (pin "1") (pinfunction "1_1") (pintype "passive"))
      (node (ref "IC4") (pin "39") (pinfunction "VDDA_39") (pintype "power_in"))
      (node (ref "L1") (pin "P$2") (pinfunction "2_P$2") (pintype "passive"))
      (node (ref "R18") (pin "2") (pinfunction "2_2") (pintype "passive"))
    )
    (net (code "232") (name "VLED+") (class "Default")
      (node (ref "C46") (pin "1") (pinfunction "1_1") (pintype "passive"))
      (node (ref "D2") (pin "C") (pinfunction "C_C") (pintype "passive"))
      (node (ref "LCD1") (pin "2") (pinfunction "VLED+_2") (pintype "power_in"))
      (node (ref "ZD3") (pin "C") (pinfunction "C_C") (pintype "passive"))
    )
    (net (code "233") (name "VLED-") (class "Default")
      (node (ref "IC11") (pin "3") (pinfunction "FB_3") (pintype "input"))
      (node (ref "LCD1") (pin "1") (pinfunction "VLED-_1") (pintype "power_in"))
      (node (ref "R30") (pin "1") (pinfunction "1_1") (pintype "passive"))
      (node (ref "ZD3") (pin "A") (pinfunction "A_A") (pintype "passive"))
    )
    (net (code "234") (name "VREF+") (class "Default")
      (node (ref "IC4") (pin "38") (pinfunction "VREF+_38") (pintype "power_in"))
      (node (ref "R18") (pin "1") (pinfunction "1_1") (pintype "passive"))
    )
    (net (code "235") (name "unconnected-(IC4C-DSI_CKN-Pad105)") (class "Default")
      (node (ref "IC4") (pin "105") (pinfunction "DSI_CKN_105") (pintype "bidirectional"))
    )
    (net (code "236") (name "unconnected-(IC4C-DSI_CKP-Pad104)") (class "Default")
      (node (ref "IC4") (pin "104") (pinfunction "DSI_CKP_104") (pintype "bidirectional"))
    )
    (net (code "237") (name "unconnected-(IC4C-DSI_D0N-Pad102)") (class "Default")
      (node (ref "IC4") (pin "102") (pinfunction "DSI_D0N_102") (pintype "bidirectional"))
    )
    (net (code "238") (name "unconnected-(IC4C-DSI_D0P-Pad101)") (class "Default")
      (node (ref "IC4") (pin "101") (pinfunction "DSI_D0P_101") (pintype "bidirectional"))
    )
    (net (code "239") (name "unconnected-(IC4C-DSI_D1N-Pad108)") (class "Default")
      (node (ref "IC4") (pin "108") (pinfunction "DSI_D1N_108") (pintype "bidirectional"))
    )
    (net (code "240") (name "unconnected-(IC4C-DSI_D1P-Pad107)") (class "Default")
      (node (ref "IC4") (pin "107") (pinfunction "DSI_D1P_107") (pintype "bidirectional"))
    )
    (net (code "241") (name "unconnected-(IC6-IO2-Pad2)") (class "Default")
      (node (ref "IC6") (pin "2") (pinfunction "IO2_2") (pintype "bidirectional"))
    )
    (net (code "242") (name "unconnected-(IC7-IO2-Pad2)") (class "Default")
      (node (ref "IC7") (pin "2") (pinfunction "IO2_2") (pintype "bidirectional"))
    )
    (net (code "243") (name "unconnected-(IC8-A12{slash}NC-36-Pad36)") (class "Default")
      (node (ref "IC8") (pin "36") (pinfunction "A12/NC-36_36") (pintype "passive"))
    )
    (net (code "244") (name "unconnected-(IC8-NC-40-Pad40)") (class "Default")
      (node (ref "IC8") (pin "40") (pinfunction "NC-40_40") (pintype "no_connect"))
    )
    (net (code "245") (name "unconnected-(IC12-IO2-Pad2)") (class "Default")
      (node (ref "IC12") (pin "2") (pinfunction "IO2_2") (pintype "bidirectional"))
    )
    (net (code "246") (name "unconnected-(IC12-IO4-Pad5)") (class "Default")
      (node (ref "IC12") (pin "5") (pinfunction "IO4_5") (pintype "bidirectional"))
    )
    (net (code "247") (name "unconnected-(IC15-SS-Pad8)") (class "Default")
      (node (ref "IC15") (pin "8") (pinfunction "SS_8") (pintype "bidirectional"))
    )
    (net (code "248") (name "unconnected-(IC17-CLK_OUT-Pad25)") (class "Default")
      (node (ref "IC17") (pin "25") (pinfunction "CLK_OUT_25") (pintype "output"))
    )
    (net (code "249") (name "unconnected-(IC17-TCK-Pad8)") (class "Default")
      (node (ref "IC17") (pin "8") (pinfunction "TCK_8") (pintype "input"))
    )
    (net (code "250") (name "unconnected-(IC17-TDI-Pad12)") (class "Default")
      (node (ref "IC17") (pin "12") (pinfunction "TDI_12") (pintype "input"))
    )
    (net (code "251") (name "unconnected-(IC17-TDO-Pad9)") (class "Default")
      (node (ref "IC17") (pin "9") (pinfunction "TDO_9") (pintype "output"))
    )
    (net (code "252") (name "unconnected-(IC17-TMS-Pad10)") (class "Default")
      (node (ref "IC17") (pin "10") (pinfunction "TMS_10") (pintype "input"))
    )
    (net (code "253") (name "unconnected-(IC17-X2-Pad33)") (class "Default")
      (node (ref "IC17") (pin "33") (pinfunction "X2_33") (pintype "output"))
    )
    (net (code "254") (name "unconnected-(IC17-~{TRST}-Pad11)") (class "Default")
      (node (ref "IC17") (pin "11") (pinfunction "~{TRST}_11") (pintype "input"))
    )
    (net (code "255") (name "unconnected-(J1-CD{slash}DAT3-Pad2)") (class "Default")
      (node (ref "J1") (pin "2") (pinfunction "CD/DAT3_2") (pintype "passive"))
    )
    (net (code "256") (name "unconnected-(J1-DAT1-Pad8)") (class "Default")
      (node (ref "J1") (pin "8") (pinfunction "DAT1_8") (pintype "passive"))
    )
    (net (code "257") (name "unconnected-(J1-DAT2-Pad1)") (class "Default")
      (node (ref "J1") (pin "1") (pinfunction "DAT2_1") (pintype "passive"))
    )
    (net (code "258") (name "unconnected-(LCD1-NC1-Pad35)") (class "Default")
      (node (ref "LCD1") (pin "35") (pinfunction "NC1_35") (pintype "no_connect"))
    )
    (net (code "259") (name "~{AUDIO_SHDN}") (class "Default")
      (node (ref "IC13") (pin "1") (pinfunction "~{SHDN}_1") (pintype "input"))
      (node (ref "R40") (pin "1") (pinfunction "1_1") (pintype "passive"))
    )
    (net (code "260") (name "~{FAULT}") (class "Default")
      (node (ref "IC3") (pin "1") (pinfunction "~{FAULT}_1") (pintype "output"))
      (node (ref "IC4") (pin "58") (pinfunction "PB2_58") (pintype "bidirectional"))
      (node (ref "R13") (pin "2") (pinfunction "2_2") (pintype "passive"))
      (node (ref "X1") (pin "26") (pinfunction "1_26") (pintype "passive"))
      (node (ref "X2") (pin "15") (pinfunction "1_15") (pintype "passive"))
    )
    (net (code "261") (name "~{RESET}") (class "Default")
      (node (ref "IC17") (pin "29") (pinfunction "RESET_N_29") (pintype "input"))
      (node (ref "IC3") (pin "4") (pinfunction "ENA_4") (pintype "input"))
      (node (ref "IC4") (pin "31") (pinfunction "NRST_31") (pintype "bidirectional"))
      (node (ref "IC7") (pin "4") (pinfunction "IO3_4") (pintype "bidirectional"))
      (node (ref "JP4") (pin "NC") (pinfunction "NC_NC") (pintype "passive"))
      (node (ref "R11") (pin "2") (pinfunction "2_2") (pintype "passive"))
      (node (ref "X1") (pin "24") (pinfunction "1_24") (pintype "passive"))
      (node (ref "X4") (pin "15") (pinfunction "1_15") (pintype "passive"))
    )
    (net (code "262") (name "~{USB_OTG_FS_OC}") (class "Default")
      (node (ref "IC10") (pin "3") (pinfunction "~{OC}_3") (pintype "passive"))
      (node (ref "IC4") (pin "146") (pinfunction "PD4_146") (pintype "bidirectional"))
      (node (ref "R31") (pin "1") (pinfunction "1_1") (pintype "passive"))
    )
  )
)
